# MotherForSmoothie_prefinal.net
KiCad netlist of a schematic drawn in EAGLE
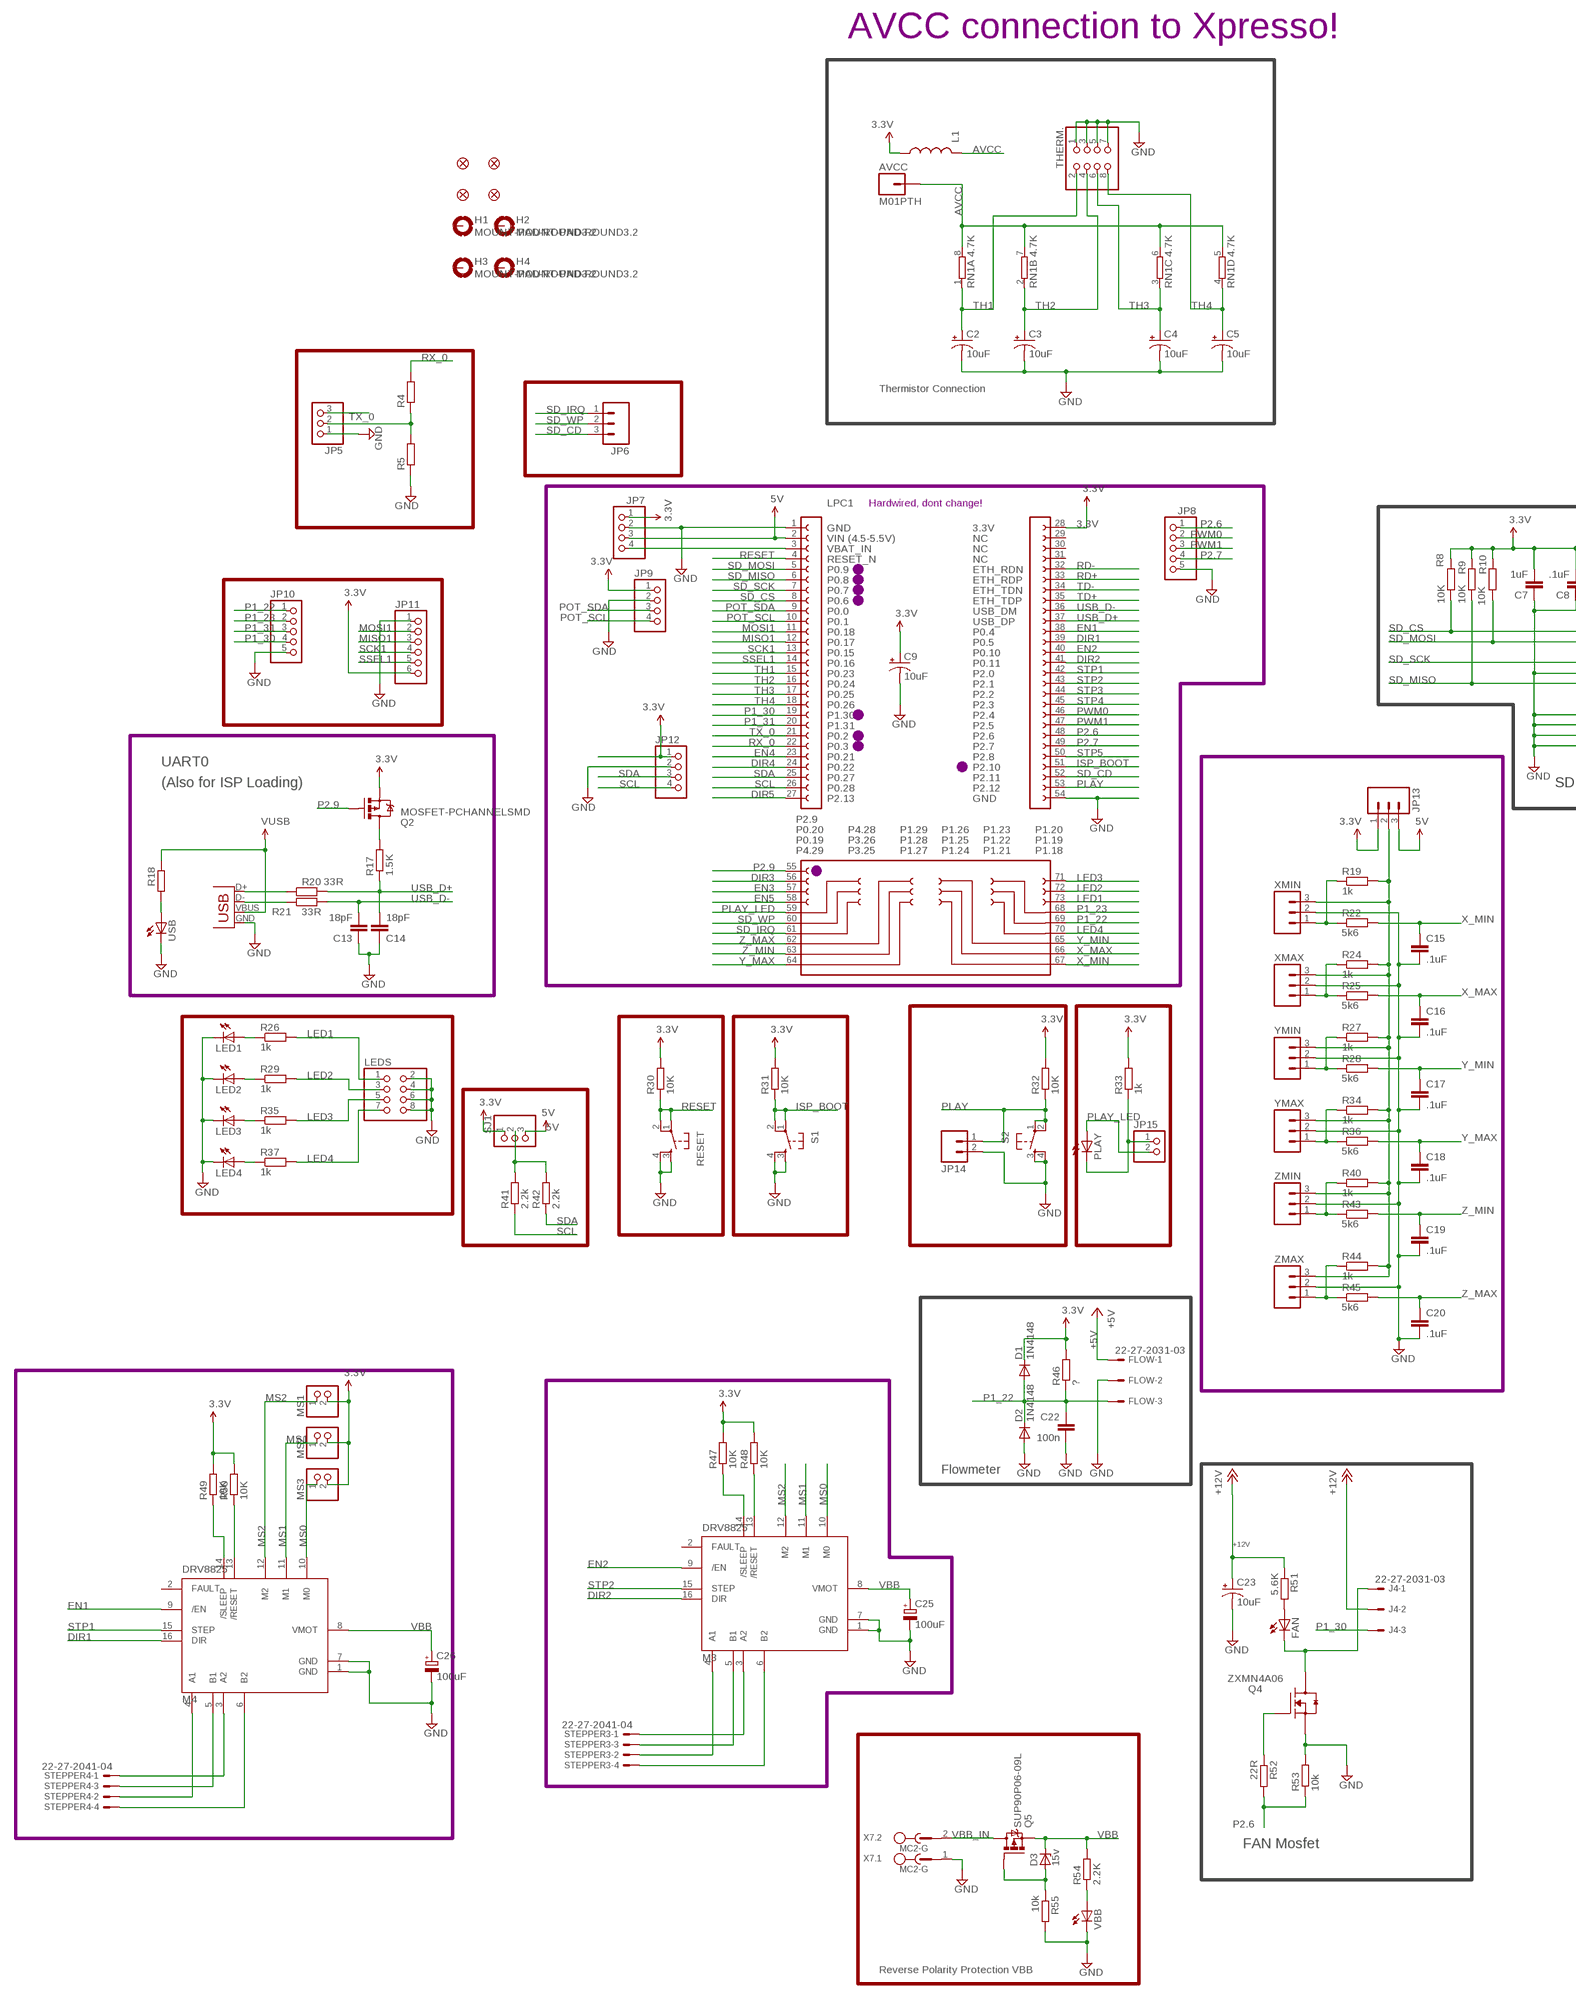
[diagram p0: schematic, sheet 1, part 1 of 2]
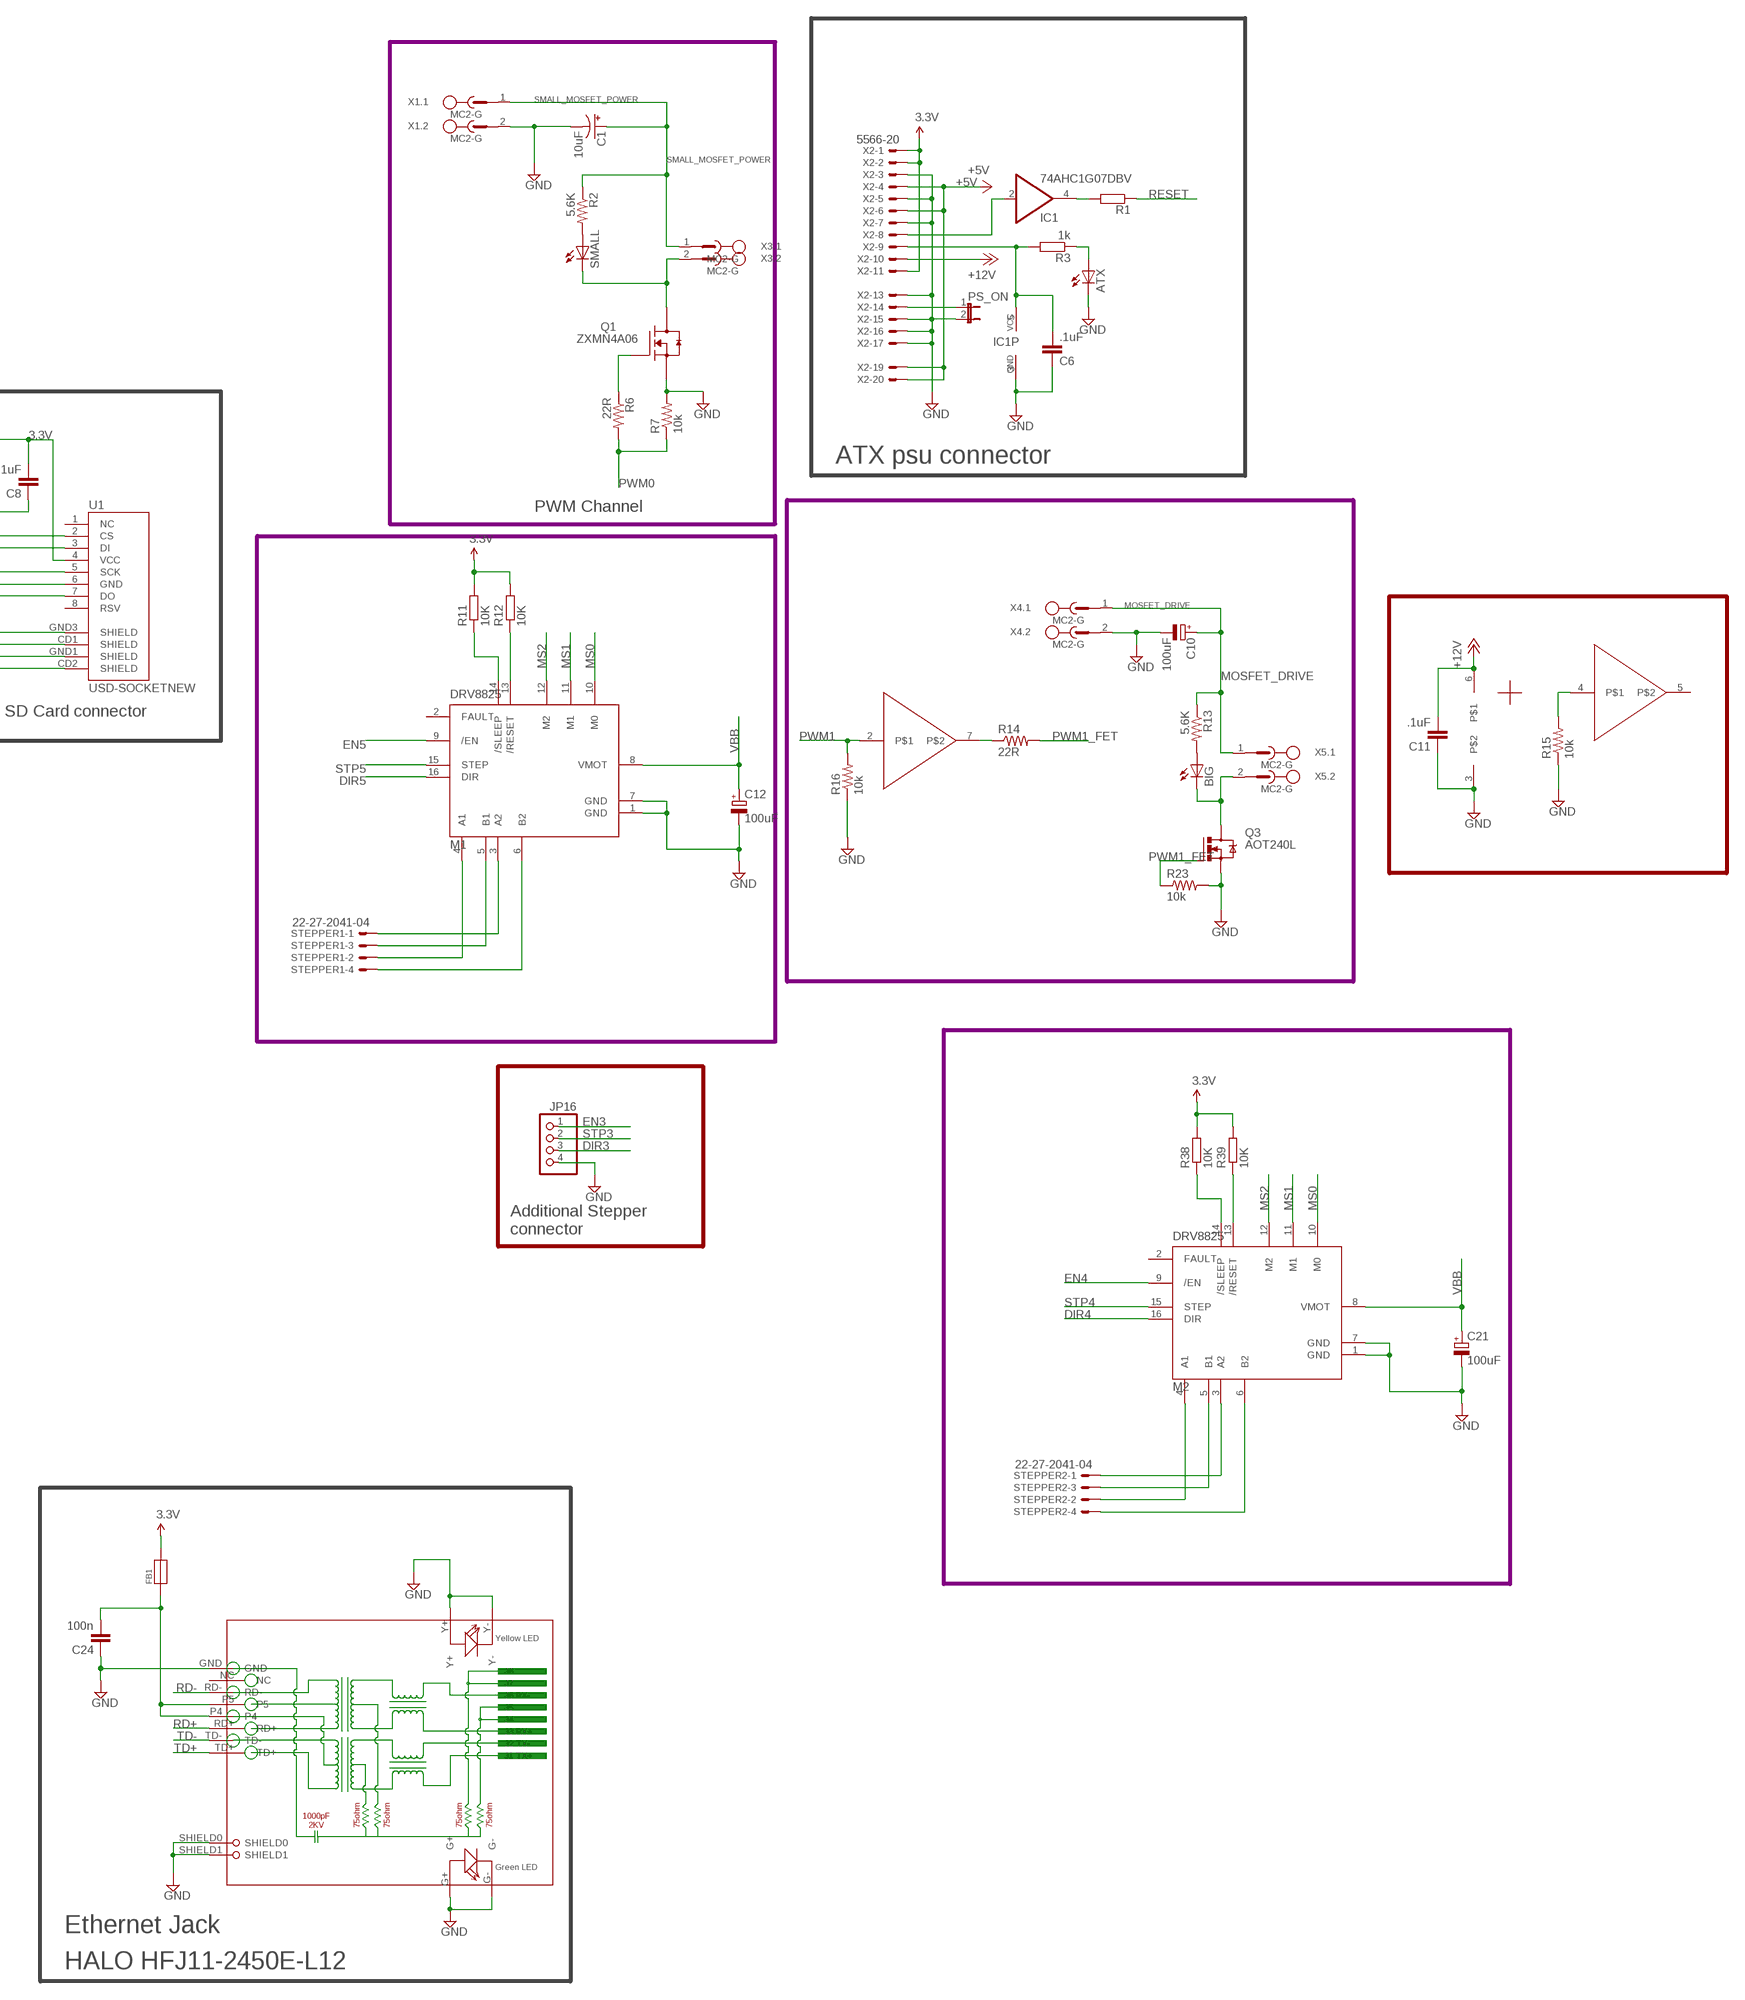
[diagram p1: schematic, sheet 1, part 2 of 2]

(export (version "E")
  (design (tool "Eeschema 10.0.6"))
  (components
    (comp (ref "ATX")
      (value "LEDCHIPLED_0805")
      (footprint "eagle-import:CHIPLED_0805")
      (libsource (lib "eagle-import") (part "LEDCHIPLED_0805"))
    )
    (comp (ref "AVCC")
      (value "M01PTH")
      (footprint "eagle-import:1X01")
      (libsource (lib "eagle-import") (part "M01PTH"))
    )
    (comp (ref "BIG")
      (value "LEDCHIP-LED0805")
      (footprint "eagle-import:CHIP-LED0805")
      (libsource (lib "eagle-import") (part "LEDCHIP-LED0805"))
    )
    (comp (ref "C1")
      (value "10uF")
      (footprint "eagle-import:EIA3216")
      (libsource (lib "eagle-import") (part "CAP_POL1206"))
    )
    (comp (ref "C2")
      (value "10uF")
      (footprint "eagle-import:EIA3216")
      (libsource (lib "eagle-import") (part "CAP_POL1206"))
    )
    (comp (ref "C3")
      (value "10uF")
      (footprint "eagle-import:EIA3216")
      (libsource (lib "eagle-import") (part "CAP_POL1206"))
    )
    (comp (ref "C4")
      (value "10uF")
      (footprint "eagle-import:EIA3216")
      (libsource (lib "eagle-import") (part "CAP_POL1206"))
    )
    (comp (ref "C5")
      (value "10uF")
      (footprint "eagle-import:EIA3216")
      (libsource (lib "eagle-import") (part "CAP_POL1206"))
    )
    (comp (ref "C6")
      (value ".1uF")
      (footprint "eagle-import:C0603")
      (libsource (lib "eagle-import") (part "C-EUC0603"))
    )
    (comp (ref "C7")
      (value "1uF")
      (footprint "eagle-import:C0603")
      (libsource (lib "eagle-import") (part "C-EUC0603"))
    )
    (comp (ref "C8")
      (value ".1uF")
      (footprint "eagle-import:C0603")
      (libsource (lib "eagle-import") (part "C-EUC0603"))
    )
    (comp (ref "C9")
      (value "10uF")
      (footprint "eagle-import:EIA3216")
      (libsource (lib "eagle-import") (part "CAP_POL1206"))
    )
    (comp (ref "C10")
      (value "100uF")
      (footprint "eagle-import:E5-8,5")
      (libsource (lib "eagle-import") (part "CPOL-EUE5-8.5"))
    )
    (comp (ref "C11")
      (value ".1uF")
      (footprint "eagle-import:C0603")
      (libsource (lib "eagle-import") (part "C-EUC0603"))
    )
    (comp (ref "C12")
      (value "100uF")
      (footprint "eagle-import:E5-8,5")
      (libsource (lib "eagle-import") (part "CPOL-EUE5-8.5"))
    )
    (comp (ref "C13")
      (value "18pF")
      (footprint "eagle-import:C0603")
      (libsource (lib "eagle-import") (part "C-EUC0603"))
    )
    (comp (ref "C14")
      (value "18pF")
      (footprint "eagle-import:C0603")
      (libsource (lib "eagle-import") (part "C-EUC0603"))
    )
    (comp (ref "C15")
      (value ".1uF")
      (footprint "eagle-import:C0603")
      (libsource (lib "eagle-import") (part "C-EUC0603"))
    )
    (comp (ref "C16")
      (value ".1uF")
      (footprint "eagle-import:C0603")
      (libsource (lib "eagle-import") (part "C-EUC0603"))
    )
    (comp (ref "C17")
      (value ".1uF")
      (footprint "eagle-import:C0603")
      (libsource (lib "eagle-import") (part "C-EUC0603"))
    )
    (comp (ref "C18")
      (value ".1uF")
      (footprint "eagle-import:C0603")
      (libsource (lib "eagle-import") (part "C-EUC0603"))
    )
    (comp (ref "C19")
      (value ".1uF")
      (footprint "eagle-import:C0603")
      (libsource (lib "eagle-import") (part "C-EUC0603"))
    )
    (comp (ref "C20")
      (value ".1uF")
      (footprint "eagle-import:C0603")
      (libsource (lib "eagle-import") (part "C-EUC0603"))
    )
    (comp (ref "C21")
      (value "100uF")
      (footprint "eagle-import:E5-8,5")
      (libsource (lib "eagle-import") (part "CPOL-EUE5-8.5"))
    )
    (comp (ref "C22")
      (value "100n")
      (footprint "eagle-import:C0603")
      (libsource (lib "eagle-import") (part "C-EUC0603"))
    )
    (comp (ref "C23")
      (value "10uF")
      (footprint "eagle-import:EIA3216")
      (libsource (lib "eagle-import") (part "CAP_POL1206"))
    )
    (comp (ref "C24")
      (value "100n")
      (footprint "eagle-import:C0603")
      (libsource (lib "eagle-import") (part "C-EUC0603"))
    )
    (comp (ref "C25")
      (value "100uF")
      (footprint "eagle-import:E5-8,5")
      (libsource (lib "eagle-import") (part "CPOL-EUE5-8.5"))
    )
    (comp (ref "C26")
      (value "100uF")
      (footprint "eagle-import:E5-8,5")
      (libsource (lib "eagle-import") (part "CPOL-EUE5-8.5"))
    )
    (comp (ref "D1")
      (value "1N4148")
      (footprint "eagle-import:MINIMELF")
      (libsource (lib "eagle-import") (part "DIODE-MINIMELF"))
    )
    (comp (ref "D2")
      (value "1N4148")
      (footprint "eagle-import:MINIMELF")
      (libsource (lib "eagle-import") (part "DIODE-MINIMELF"))
    )
    (comp (ref "D3")
      (value "15v")
      (footprint "eagle-import:SMB")
      (libsource (lib "eagle-import") (part "ZENER-DIODESMB"))
    )
    (comp (ref "FAN")
      (value "LEDCHIPLED_0805")
      (footprint "eagle-import:CHIPLED_0805")
      (libsource (lib "eagle-import") (part "LEDCHIPLED_0805"))
    )
    (comp (ref "FB1")
      (value "FERRITE")
      (footprint "eagle-import:0603")
      (libsource (lib "eagle-import") (part "FERRITE"))
    )
    (comp (ref "FLOW")
      (value "22-27-2031-03")
      (footprint "eagle-import:6410-03")
      (libsource (lib "eagle-import") (part "22-?-0327-2031"))
    )
    (comp (ref "H1")
      (value "MOUNT-PAD-ROUND3.2")
      (footprint "eagle-import:3,2-PAD")
      (libsource (lib "eagle-import") (part "MOUNT-PAD-ROUND3.2"))
    )
    (comp (ref "H2")
      (value "MOUNT-PAD-ROUND3.2")
      (footprint "eagle-import:3,2-PAD")
      (libsource (lib "eagle-import") (part "MOUNT-PAD-ROUND3.2"))
    )
    (comp (ref "H3")
      (value "MOUNT-PAD-ROUND3.2")
      (footprint "eagle-import:3,2-PAD")
      (libsource (lib "eagle-import") (part "MOUNT-PAD-ROUND3.2"))
    )
    (comp (ref "H4")
      (value "MOUNT-PAD-ROUND3.2")
      (footprint "eagle-import:3,2-PAD")
      (libsource (lib "eagle-import") (part "MOUNT-PAD-ROUND3.2"))
    )
    (comp (ref "IC1")
      (value "74AHC1G07DBV")
      (footprint "eagle-import:SOT23-5")
      (libsource (lib "eagle-import") (part "741G07DBVAHC"))
    )
    (comp (ref "IC2")
      (value "TC4427")
      (footprint "eagle-import:SOIC8")
      (libsource (lib "eagle-import") (part "TC4427"))
    )
    (comp (ref "J4")
      (value "22-27-2031-03")
      (footprint "eagle-import:6410-03")
      (libsource (lib "eagle-import") (part "22-?-0327-2031"))
    )
    (comp (ref "JP1")
      (value "FIDUCIAL1X2")
      (footprint "eagle-import:FIDUCIAL-1X2")
      (libsource (lib "eagle-import") (part "FIDUCIAL1X2"))
    )
    (comp (ref "JP2")
      (value "FIDUCIAL1X2")
      (footprint "eagle-import:FIDUCIAL-1X2")
      (libsource (lib "eagle-import") (part "FIDUCIAL1X2"))
    )
    (comp (ref "JP3")
      (value "FIDUCIAL1X2")
      (footprint "eagle-import:FIDUCIAL-1X2")
      (libsource (lib "eagle-import") (part "FIDUCIAL1X2"))
    )
    (comp (ref "JP4")
      (value "FIDUCIAL1X2")
      (footprint "eagle-import:FIDUCIAL-1X2")
      (libsource (lib "eagle-import") (part "FIDUCIAL1X2"))
    )
    (comp (ref "JP5")
      (value "PINHD-1X3_2.54-SMD")
      (footprint "eagle-import:1X03SMD")
      (libsource (lib "eagle-import") (part "PINHD-1X3_2.54-SMD"))
    )
    (comp (ref "JP6")
      (value "M031X03_NO_SILK")
      (footprint "eagle-import:1X03_NO_SILK")
      (libsource (lib "eagle-import") (part "M031X03_NO_SILK"))
    )
    (comp (ref "JP7")
      (value "PINHD-1X4_2.54-SMD")
      (footprint "eagle-import:1X04SMD")
      (libsource (lib "eagle-import") (part "PINHD-1X4_2.54-SMD"))
    )
    (comp (ref "JP8")
      (value "PINHD-1X5_2.54-SMD")
      (footprint "eagle-import:1X05SMD")
      (libsource (lib "eagle-import") (part "PINHD-1X5_2.54-SMD"))
    )
    (comp (ref "JP9")
      (value "PINHD-1X4_2.54-SMD")
      (footprint "eagle-import:1X04SMD")
      (libsource (lib "eagle-import") (part "PINHD-1X4_2.54-SMD"))
    )
    (comp (ref "JP10")
      (value "PINHD-1X5_2.54-SMD")
      (footprint "eagle-import:1X05SMD")
      (libsource (lib "eagle-import") (part "PINHD-1X5_2.54-SMD"))
    )
    (comp (ref "JP11")
      (value "PINHD-1X6_2.54-SMD")
      (footprint "eagle-import:1X06SMD")
      (libsource (lib "eagle-import") (part "PINHD-1X6_2.54-SMD"))
    )
    (comp (ref "JP12")
      (value "PINHD-1X4_2.54-SMD")
      (footprint "eagle-import:1X04SMD")
      (libsource (lib "eagle-import") (part "PINHD-1X4_2.54-SMD"))
    )
    (comp (ref "JP13")
      (value "M031X03_NO_SILK")
      (footprint "eagle-import:1X03_NO_SILK")
      (libsource (lib "eagle-import") (part "M031X03_NO_SILK"))
    )
    (comp (ref "JP14")
      (value "M02PTH")
      (footprint "eagle-import:1X02")
      (libsource (lib "eagle-import") (part "M02PTH"))
    )
    (comp (ref "JP15")
      (value "PINHD-1X2_2.54-SMD")
      (footprint "eagle-import:1X02SMD")
      (libsource (lib "eagle-import") (part "PINHD-1X2_2.54-SMD"))
    )
    (comp (ref "JP16")
      (value "PINHD-1X4_2.54-SMD")
      (footprint "eagle-import:1X04SMD")
      (libsource (lib "eagle-import") (part "PINHD-1X4_2.54-SMD"))
    )
    (comp (ref "L1")
      (value "INDUCTOR0603")
      (footprint "eagle-import:0603")
      (libsource (lib "eagle-import") (part "INDUCTOR0603"))
    )
    (comp (ref "LED1")
      (value "LEDCHIP-LED0805")
      (footprint "eagle-import:CHIP-LED0805")
      (libsource (lib "eagle-import") (part "LEDCHIP-LED0805"))
    )
    (comp (ref "LED2")
      (value "LEDCHIP-LED0805")
      (footprint "eagle-import:CHIP-LED0805")
      (libsource (lib "eagle-import") (part "LEDCHIP-LED0805"))
    )
    (comp (ref "LED3")
      (value "LEDCHIP-LED0805")
      (footprint "eagle-import:CHIP-LED0805")
      (libsource (lib "eagle-import") (part "LEDCHIP-LED0805"))
    )
    (comp (ref "LED4")
      (value "LEDCHIP-LED0805")
      (footprint "eagle-import:CHIP-LED0805")
      (libsource (lib "eagle-import") (part "LEDCHIP-LED0805"))
    )
    (comp (ref "LEDS")
      (value "PINHD-2X4_2.54-SMD")
      (footprint "eagle-import:2X04SMD")
      (libsource (lib "eagle-import") (part "PINHD-2X4_2.54-SMD"))
    )
    (comp (ref "LPC1")
      (value "LPCXPRESSO_LPC1769SMD_PART")
      (footprint "eagle-import:LPCXPRESSO_LPC1769_SMD")
      (libsource (lib "eagle-import") (part "LPCXPRESSO_LPC1769SMD_PART"))
    )
    (comp (ref "M1")
      (value "DRV8825")
      (footprint "eagle-import:DRV8825")
      (libsource (lib "eagle-import") (part "DRV8825"))
    )
    (comp (ref "M2")
      (value "DRV8825")
      (footprint "eagle-import:DRV8825")
      (libsource (lib "eagle-import") (part "DRV8825"))
    )
    (comp (ref "M3")
      (value "DRV8825")
      (footprint "eagle-import:DRV8825")
      (libsource (lib "eagle-import") (part "DRV8825"))
    )
    (comp (ref "M4")
      (value "DRV8825")
      (footprint "eagle-import:DRV8825")
      (libsource (lib "eagle-import") (part "DRV8825"))
    )
    (comp (ref "MS1")
      (value "PINHD-1X2_2.54-SMD")
      (footprint "eagle-import:1X02SMD")
      (libsource (lib "eagle-import") (part "PINHD-1X2_2.54-SMD"))
    )
    (comp (ref "MS2")
      (value "PINHD-1X2_2.54-SMD")
      (footprint "eagle-import:1X02SMD")
      (libsource (lib "eagle-import") (part "PINHD-1X2_2.54-SMD"))
    )
    (comp (ref "MS3")
      (value "PINHD-1X2_2.54-SMD")
      (footprint "eagle-import:1X02SMD")
      (libsource (lib "eagle-import") (part "PINHD-1X2_2.54-SMD"))
    )
    (comp (ref "PLAY")
      (value "LEDCHIPLED_0805")
      (footprint "eagle-import:CHIPLED_0805")
      (libsource (lib "eagle-import") (part "LEDCHIPLED_0805"))
    )
    (comp (ref "PS_ON")
      (value "JP1E")
      (footprint "eagle-import:JP1")
      (libsource (lib "eagle-import") (part "JP1E"))
    )
    (comp (ref "Q1")
      (value "ZXMN4A06")
      (footprint "eagle-import:SOT230P700X160-4N")
      (libsource (lib "eagle-import") (part "MOSFET-NCH_SOT-223"))
    )
    (comp (ref "Q2")
      (value "MOSFET-PCHANNELSMD")
      (footprint "eagle-import:SOT23-3")
      (libsource (lib "eagle-import") (part "MOSFET-PCHANNELSMD"))
    )
    (comp (ref "Q3")
      (value "AOT240L")
      (footprint "eagle-import:TO220BV")
      (libsource (lib "eagle-import") (part "IRF540"))
    )
    (comp (ref "Q4")
      (value "ZXMN4A06")
      (footprint "eagle-import:SOT230P700X160-4N")
      (libsource (lib "eagle-import") (part "MOSFET-NCH_SOT-223"))
    )
    (comp (ref "Q5")
      (value "SUP90P06-09L")
      (footprint "eagle-import:TO220BV")
      (libsource (lib "eagle-import") (part "IRF9530"))
    )
    (comp (ref "R1")
      (value "R-EU_R0603")
      (footprint "eagle-import:R0603")
      (libsource (lib "eagle-import") (part "R-EU_R0603"))
    )
    (comp (ref "R2")
      (value "5.6K")
      (footprint "eagle-import:R0603")
      (libsource (lib "eagle-import") (part "R-US_R0603"))
    )
    (comp (ref "R3")
      (value "1k")
      (footprint "eagle-import:R0603")
      (libsource (lib "eagle-import") (part "R-EU_R0603"))
    )
    (comp (ref "R4")
      (value "R-EU_R0603")
      (footprint "eagle-import:R0603")
      (libsource (lib "eagle-import") (part "R-EU_R0603"))
    )
    (comp (ref "R5")
      (value "R-EU_R0603")
      (footprint "eagle-import:R0603")
      (libsource (lib "eagle-import") (part "R-EU_R0603"))
    )
    (comp (ref "R6")
      (value "22R")
      (footprint "eagle-import:R0603")
      (libsource (lib "eagle-import") (part "R-US_R0603"))
    )
    (comp (ref "R7")
      (value "10k")
      (footprint "eagle-import:R0603")
      (libsource (lib "eagle-import") (part "R-US_R0603"))
    )
    (comp (ref "R8")
      (value "10K")
      (footprint "eagle-import:R0603")
      (libsource (lib "eagle-import") (part "R-EU_R0603"))
    )
    (comp (ref "R9")
      (value "10K")
      (footprint "eagle-import:R0603")
      (libsource (lib "eagle-import") (part "R-EU_R0603"))
    )
    (comp (ref "R10")
      (value "10K")
      (footprint "eagle-import:R0603")
      (libsource (lib "eagle-import") (part "R-EU_R0603"))
    )
    (comp (ref "R11")
      (value "10K")
      (footprint "eagle-import:R0603")
      (libsource (lib "eagle-import") (part "R-EU_R0603"))
    )
    (comp (ref "R12")
      (value "10K")
      (footprint "eagle-import:R0603")
      (libsource (lib "eagle-import") (part "R-EU_R0603"))
    )
    (comp (ref "R13")
      (value "5.6K")
      (footprint "eagle-import:R0603")
      (libsource (lib "eagle-import") (part "R-US_R0603"))
    )
    (comp (ref "R14")
      (value "22R")
      (footprint "eagle-import:R0603")
      (libsource (lib "eagle-import") (part "R-US_R0603"))
    )
    (comp (ref "R15")
      (value "10k")
      (footprint "eagle-import:R0603")
      (libsource (lib "eagle-import") (part "R-US_R0603"))
    )
    (comp (ref "R16")
      (value "10k")
      (footprint "eagle-import:R0603")
      (libsource (lib "eagle-import") (part "R-US_R0603"))
    )
    (comp (ref "R17")
      (value "1.5K")
      (footprint "eagle-import:R0603")
      (libsource (lib "eagle-import") (part "R-EU_R0603"))
    )
    (comp (ref "R18")
      (value "R-EU_R0603")
      (footprint "eagle-import:R0603")
      (libsource (lib "eagle-import") (part "R-EU_R0603"))
    )
    (comp (ref "R19")
      (value "1k")
      (footprint "eagle-import:R0603")
      (libsource (lib "eagle-import") (part "R-EU_R0603"))
    )
    (comp (ref "R20")
      (value "33R")
      (footprint "eagle-import:R0603")
      (libsource (lib "eagle-import") (part "R-EU_R0603"))
    )
    (comp (ref "R21")
      (value "33R")
      (footprint "eagle-import:R0603")
      (libsource (lib "eagle-import") (part "R-EU_R0603"))
    )
    (comp (ref "R22")
      (value "5k6")
      (footprint "eagle-import:R0603")
      (libsource (lib "eagle-import") (part "R-EU_R0603"))
    )
    (comp (ref "R23")
      (value "10k")
      (footprint "eagle-import:R0603")
      (libsource (lib "eagle-import") (part "R-US_R0603"))
    )
    (comp (ref "R24")
      (value "1k")
      (footprint "eagle-import:R0603")
      (libsource (lib "eagle-import") (part "R-EU_R0603"))
    )
    (comp (ref "R25")
      (value "5k6")
      (footprint "eagle-import:R0603")
      (libsource (lib "eagle-import") (part "R-EU_R0603"))
    )
    (comp (ref "R26")
      (value "1k")
      (footprint "eagle-import:R0603")
      (libsource (lib "eagle-import") (part "R-EU_R0603"))
    )
    (comp (ref "R27")
      (value "1k")
      (footprint "eagle-import:R0603")
      (libsource (lib "eagle-import") (part "R-EU_R0603"))
    )
    (comp (ref "R28")
      (value "5k6")
      (footprint "eagle-import:R0603")
      (libsource (lib "eagle-import") (part "R-EU_R0603"))
    )
    (comp (ref "R29")
      (value "1k")
      (footprint "eagle-import:R0603")
      (libsource (lib "eagle-import") (part "R-EU_R0603"))
    )
    (comp (ref "R30")
      (value "10K")
      (footprint "eagle-import:R0603")
      (libsource (lib "eagle-import") (part "R-EU_R0603"))
    )
    (comp (ref "R31")
      (value "10K")
      (footprint "eagle-import:R0603")
      (libsource (lib "eagle-import") (part "R-EU_R0603"))
    )
    (comp (ref "R32")
      (value "10K")
      (footprint "eagle-import:R0603")
      (libsource (lib "eagle-import") (part "R-EU_R0603"))
    )
    (comp (ref "R33")
      (value "1k")
      (footprint "eagle-import:R0603")
      (libsource (lib "eagle-import") (part "R-EU_R0603"))
    )
    (comp (ref "R34")
      (value "1k")
      (footprint "eagle-import:R0603")
      (libsource (lib "eagle-import") (part "R-EU_R0603"))
    )
    (comp (ref "R35")
      (value "1k")
      (footprint "eagle-import:R0603")
      (libsource (lib "eagle-import") (part "R-EU_R0603"))
    )
    (comp (ref "R36")
      (value "5k6")
      (footprint "eagle-import:R0603")
      (libsource (lib "eagle-import") (part "R-EU_R0603"))
    )
    (comp (ref "R37")
      (value "1k")
      (footprint "eagle-import:R0603")
      (libsource (lib "eagle-import") (part "R-EU_R0603"))
    )
    (comp (ref "R38")
      (value "10K")
      (footprint "eagle-import:R0603")
      (libsource (lib "eagle-import") (part "R-EU_R0603"))
    )
    (comp (ref "R39")
      (value "10K")
      (footprint "eagle-import:R0603")
      (libsource (lib "eagle-import") (part "R-EU_R0603"))
    )
    (comp (ref "R40")
      (value "1k")
      (footprint "eagle-import:R0603")
      (libsource (lib "eagle-import") (part "R-EU_R0603"))
    )
    (comp (ref "R41")
      (value "2.2k")
      (footprint "eagle-import:R0603")
      (libsource (lib "eagle-import") (part "R-EU_R0603"))
    )
    (comp (ref "R42")
      (value "2.2k")
      (footprint "eagle-import:R0603")
      (libsource (lib "eagle-import") (part "R-EU_R0603"))
    )
    (comp (ref "R43")
      (value "5k6")
      (footprint "eagle-import:R0603")
      (libsource (lib "eagle-import") (part "R-EU_R0603"))
    )
    (comp (ref "R44")
      (value "1k")
      (footprint "eagle-import:R0603")
      (libsource (lib "eagle-import") (part "R-EU_R0603"))
    )
    (comp (ref "R45")
      (value "5k6")
      (footprint "eagle-import:R0603")
      (libsource (lib "eagle-import") (part "R-EU_R0603"))
    )
    (comp (ref "R46")
      (value "?")
      (footprint "eagle-import:R0603")
      (libsource (lib "eagle-import") (part "R-EU_R0603"))
    )
    (comp (ref "R47")
      (value "10K")
      (footprint "eagle-import:R0603")
      (libsource (lib "eagle-import") (part "R-EU_R0603"))
    )
    (comp (ref "R48")
      (value "10K")
      (footprint "eagle-import:R0603")
      (libsource (lib "eagle-import") (part "R-EU_R0603"))
    )
    (comp (ref "R49")
      (value "10K")
      (footprint "eagle-import:R0603")
      (libsource (lib "eagle-import") (part "R-EU_R0603"))
    )
    (comp (ref "R50")
      (value "10K")
      (footprint "eagle-import:R0603")
      (libsource (lib "eagle-import") (part "R-EU_R0603"))
    )
    (comp (ref "R51")
      (value "5.6K")
      (footprint "eagle-import:R0603")
      (libsource (lib "eagle-import") (part "R-EU_R0603"))
    )
    (comp (ref "R52")
      (value "22R")
      (footprint "eagle-import:R0603")
      (libsource (lib "eagle-import") (part "R-EU_R0603"))
    )
    (comp (ref "R53")
      (value "10k")
      (footprint "eagle-import:R0603")
      (libsource (lib "eagle-import") (part "R-EU_R0603"))
    )
    (comp (ref "R54")
      (value "2.2K")
      (footprint "eagle-import:R0603")
      (libsource (lib "eagle-import") (part "R-EU_R0603"))
    )
    (comp (ref "R55")
      (value "10k")
      (footprint "eagle-import:R0603")
      (libsource (lib "eagle-import") (part "R-EU_R0603"))
    )
    (comp (ref "RESET")
      (value "TAC_SWITCHSMD")
      (footprint "eagle-import:TACTILE_SWITCH_SMD")
      (libsource (lib "eagle-import") (part "TAC_SWITCHSMD"))
    )
    (comp (ref "RJ1")
      (value "HR911105A")
      (footprint "eagle-import:HR911105A")
      (libsource (lib "eagle-import") (part "HR911105A"))
    )
    (comp (ref "RN1")
      (value "4.7K")
      (footprint "eagle-import:0603-ARV")
      (libsource (lib "eagle-import") (part "4R-N0603-ARV"))
    )
    (comp (ref "S1")
      (value "TAC_SWITCHSMD")
      (footprint "eagle-import:TACTILE_SWITCH_SMD")
      (libsource (lib "eagle-import") (part "TAC_SWITCHSMD"))
    )
    (comp (ref "S2")
      (value "TAC_SWITCHSMD")
      (footprint "eagle-import:TACTILE_SWITCH_SMD")
      (libsource (lib "eagle-import") (part "TAC_SWITCHSMD"))
    )
    (comp (ref "SJ1")
      (value "PINHD-1X3_2.54-SMD")
      (footprint "eagle-import:1X03SMD")
      (libsource (lib "eagle-import") (part "PINHD-1X3_2.54-SMD"))
    )
    (comp (ref "SMALL")
      (value "LEDCHIP-LED0805")
      (footprint "eagle-import:CHIP-LED0805")
      (libsource (lib "eagle-import") (part "LEDCHIP-LED0805"))
    )
    (comp (ref "STEPPER1")
      (value "22-27-2041-04")
      (footprint "eagle-import:6410-04")
      (libsource (lib "eagle-import") (part "22-?-0427-2041"))
    )
    (comp (ref "STEPPER2")
      (value "22-27-2041-04")
      (footprint "eagle-import:6410-04")
      (libsource (lib "eagle-import") (part "22-?-0427-2041"))
    )
    (comp (ref "STEPPER3")
      (value "22-27-2041-04")
      (footprint "eagle-import:6410-04")
      (libsource (lib "eagle-import") (part "22-?-0427-2041"))
    )
    (comp (ref "STEPPER4")
      (value "22-27-2041-04")
      (footprint "eagle-import:6410-04")
      (libsource (lib "eagle-import") (part "22-?-0427-2041"))
    )
    (comp (ref "THERM.")
      (value "PINHD-2X4MICROMATCH-SMD")
      (footprint "eagle-import:SMDTOP8")
      (libsource (lib "eagle-import") (part "PINHD-2X4MICROMATCH-SMD"))
    )
    (comp (ref "U1")
      (value "USD-SOCKETNEW")
      (footprint "eagle-import:MICRO-SD-SOCKET-PP")
      (libsource (lib "eagle-import") (part "USD-SOCKETNEW"))
    )
    (comp (ref "USB")
      (value "LEDCHIPLED_0805")
      (footprint "eagle-import:CHIPLED_0805")
      (libsource (lib "eagle-import") (part "LEDCHIPLED_0805"))
    )
    (comp (ref "VBB")
      (value "LEDCHIPLED_0805")
      (footprint "eagle-import:CHIPLED_0805")
      (libsource (lib "eagle-import") (part "LEDCHIPLED_0805"))
    )
    (comp (ref "X1")
      (value "MC2-G")
      (footprint "eagle-import:MC2-G")
      (libsource (lib "eagle-import") (part "MC2-G"))
    )
    (comp (ref "X2")
      (value "5566-20")
      (footprint "eagle-import:5566-20")
      (libsource (lib "eagle-import") (part "5566-20"))
    )
    (comp (ref "X3")
      (value "MC2-G")
      (footprint "eagle-import:MC2-G")
      (libsource (lib "eagle-import") (part "MC2-G"))
    )
    (comp (ref "X4")
      (value "MC2-G")
      (footprint "eagle-import:MC2-G")
      (libsource (lib "eagle-import") (part "MC2-G"))
    )
    (comp (ref "X5")
      (value "MC2-G")
      (footprint "eagle-import:MC2-G")
      (libsource (lib "eagle-import") (part "MC2-G"))
    )
    (comp (ref "X6")
      (value "USB-MICROB")
      (footprint "eagle-import:USB-MICROB")
      (libsource (lib "eagle-import") (part "USB-MICROB"))
    )
    (comp (ref "X7")
      (value "MC2-G")
      (footprint "eagle-import:MC2-G")
      (libsource (lib "eagle-import") (part "MC2-G"))
    )
    (comp (ref "XMAX")
      (value "M031X03_NO_SILK")
      (footprint "eagle-import:1X03_NO_SILK")
      (libsource (lib "eagle-import") (part "M031X03_NO_SILK"))
    )
    (comp (ref "XMIN")
      (value "M031X03_NO_SILK")
      (footprint "eagle-import:1X03_NO_SILK")
      (libsource (lib "eagle-import") (part "M031X03_NO_SILK"))
    )
    (comp (ref "YMAX")
      (value "M031X03_NO_SILK")
      (footprint "eagle-import:1X03_NO_SILK")
      (libsource (lib "eagle-import") (part "M031X03_NO_SILK"))
    )
    (comp (ref "YMIN")
      (value "M031X03_NO_SILK")
      (footprint "eagle-import:1X03_NO_SILK")
      (libsource (lib "eagle-import") (part "M031X03_NO_SILK"))
    )
    (comp (ref "ZMAX")
      (value "M031X03_NO_SILK")
      (footprint "eagle-import:1X03_NO_SILK")
      (libsource (lib "eagle-import") (part "M031X03_NO_SILK"))
    )
    (comp (ref "ZMIN")
      (value "M031X03_NO_SILK")
      (footprint "eagle-import:1X03_NO_SILK")
      (libsource (lib "eagle-import") (part "M031X03_NO_SILK"))
    )
  )
  (nets
    (net (code "1") (name "+5V") (class "Default")
      (node (ref "FLOW") (pin "1") (pinfunction "S_1") (pintype "passive"))
      (node (ref "X2") (pin "19") (pinfunction "S_19") (pintype "passive"))
      (node (ref "X2") (pin "20") (pinfunction "S_20") (pintype "passive"))
      (node (ref "X2") (pin "4") (pinfunction "S_4") (pintype "passive"))
      (node (ref "X2") (pin "6") (pinfunction "S_6") (pintype "passive"))
    )
    (net (code "2") (name "+12V") (class "Default")
      (node (ref "C11") (pin "2") (pinfunction "2_2") (pintype "passive"))
      (node (ref "C23") (pin "A") (pinfunction "+_A") (pintype "passive"))
      (node (ref "IC2") (pin "6") (pinfunction "P$1_6") (pintype "bidirectional"))
      (node (ref "J4") (pin "2") (pinfunction "S_2") (pintype "passive"))
      (node (ref "R51") (pin "1") (pinfunction "1_1") (pintype "passive"))
      (node (ref "X2") (pin "10") (pinfunction "S_10") (pintype "passive"))
    )
    (net (code "3") (name "/AVCC") (class "Default")
      (node (ref "AVCC") (pin "1") (pinfunction "1_1") (pintype "passive"))
      (node (ref "L1") (pin "1") (pinfunction "1_1") (pintype "passive"))
      (node (ref "RN1") (pin "5") (pinfunction "2_5") (pintype "passive"))
      (node (ref "RN1") (pin "6") (pinfunction "2_6") (pintype "passive"))
      (node (ref "RN1") (pin "7") (pinfunction "2_7") (pintype "passive"))
      (node (ref "RN1") (pin "8") (pinfunction "2_8") (pintype "passive"))
    )
    (net (code "4") (name "/DIR1") (class "Default")
      (node (ref "LPC1") (pin "39") (pinfunction "39_39") (pintype "passive"))
      (node (ref "M4") (pin "16") (pinfunction "DIR_16") (pintype "input"))
    )
    (net (code "5") (name "/DIR2") (class "Default")
      (node (ref "LPC1") (pin "41") (pinfunction "41_41") (pintype "passive"))
      (node (ref "M3") (pin "16") (pinfunction "DIR_16") (pintype "input"))
    )
    (net (code "6") (name "/DIR3") (class "Default")
      (node (ref "JP16") (pin "3") (pinfunction "3_3") (pintype "passive"))
      (node (ref "LPC1") (pin "56") (pinfunction "56_56") (pintype "passive"))
    )
    (net (code "7") (name "/DIR4") (class "Default")
      (node (ref "LPC1") (pin "24") (pinfunction "24_24") (pintype "passive"))
      (node (ref "M2") (pin "16") (pinfunction "DIR_16") (pintype "input"))
    )
    (net (code "8") (name "/DIR5") (class "Default")
      (node (ref "LPC1") (pin "27") (pinfunction "27_27") (pintype "passive"))
      (node (ref "M1") (pin "16") (pinfunction "DIR_16") (pintype "input"))
    )
    (net (code "9") (name "/EN1") (class "Default")
      (node (ref "LPC1") (pin "38") (pinfunction "38_38") (pintype "passive"))
      (node (ref "M4") (pin "9") (pinfunction "/EN_9") (pintype "input"))
    )
    (net (code "10") (name "/EN2") (class "Default")
      (node (ref "LPC1") (pin "40") (pinfunction "40_40") (pintype "passive"))
      (node (ref "M3") (pin "9") (pinfunction "/EN_9") (pintype "input"))
    )
    (net (code "11") (name "/EN3") (class "Default")
      (node (ref "JP16") (pin "1") (pinfunction "1_1") (pintype "passive"))
      (node (ref "LPC1") (pin "57") (pinfunction "57_57") (pintype "passive"))
    )
    (net (code "12") (name "/EN4") (class "Default")
      (node (ref "LPC1") (pin "23") (pinfunction "23_23") (pintype "passive"))
      (node (ref "M2") (pin "9") (pinfunction "/EN_9") (pintype "input"))
    )
    (net (code "13") (name "/EN5") (class "Default")
      (node (ref "LPC1") (pin "58") (pinfunction "58_58") (pintype "passive"))
      (node (ref "M1") (pin "9") (pinfunction "/EN_9") (pintype "input"))
    )
    (net (code "14") (name "/ISP_BOOT") (class "Default")
      (node (ref "LPC1") (pin "51") (pinfunction "51_51") (pintype "passive"))
      (node (ref "R31") (pin "1") (pinfunction "1_1") (pintype "passive"))
      (node (ref "S1") (pin "1") (pinfunction "1_1") (pintype "passive"))
      (node (ref "S1") (pin "2") (pinfunction "2_2") (pintype "passive"))
    )
    (net (code "15") (name "/LED1") (class "Default")
      (node (ref "LEDS") (pin "1") (pinfunction "1_1") (pintype "passive"))
      (node (ref "LPC1") (pin "73") (pinfunction "73_73") (pintype "passive"))
      (node (ref "R26") (pin "2") (pinfunction "2_2") (pintype "passive"))
    )
    (net (code "16") (name "/LED2") (class "Default")
      (node (ref "LEDS") (pin "3") (pinfunction "3_3") (pintype "passive"))
      (node (ref "LPC1") (pin "72") (pinfunction "72_72") (pintype "passive"))
      (node (ref "R29") (pin "2") (pinfunction "2_2") (pintype "passive"))
    )
    (net (code "17") (name "/LED3") (class "Default")
      (node (ref "LEDS") (pin "5") (pinfunction "5_5") (pintype "passive"))
      (node (ref "LPC1") (pin "71") (pinfunction "71_71") (pintype "passive"))
      (node (ref "R35") (pin "2") (pinfunction "2_2") (pintype "passive"))
    )
    (net (code "18") (name "/LED4") (class "Default")
      (node (ref "LEDS") (pin "7") (pinfunction "7_7") (pintype "passive"))
      (node (ref "LPC1") (pin "70") (pinfunction "70_70") (pintype "passive"))
      (node (ref "R37") (pin "2") (pinfunction "2_2") (pintype "passive"))
    )
    (net (code "19") (name "/MISO1") (class "Default")
      (node (ref "JP11") (pin "3") (pinfunction "3_3") (pintype "passive"))
      (node (ref "LPC1") (pin "12") (pinfunction "12_12") (pintype "passive"))
    )
    (net (code "20") (name "/MOSFET_DRIVE") (class "Default")
      (node (ref "C10") (pin "+") (pinfunction "+_+") (pintype "passive"))
      (node (ref "R13") (pin "1") (pinfunction "1_1") (pintype "passive"))
      (node (ref "X4") (pin "1") (pinfunction "SK_1") (pintype "passive"))
      (node (ref "X5") (pin "1") (pinfunction "SK_1") (pintype "passive"))
    )
    (net (code "21") (name "/MOSI1") (class "Default")
      (node (ref "JP11") (pin "2") (pinfunction "2_2") (pintype "passive"))
      (node (ref "LPC1") (pin "11") (pinfunction "11_11") (pintype "passive"))
    )
    (net (code "22") (name "/MS0") (class "Default")
      (node (ref "M1") (pin "10") (pinfunction "M0_10") (pintype "input"))
      (node (ref "M2") (pin "10") (pinfunction "M0_10") (pintype "input"))
      (node (ref "M3") (pin "10") (pinfunction "M0_10") (pintype "input"))
      (node (ref "M4") (pin "10") (pinfunction "M0_10") (pintype "input"))
      (node (ref "MS3") (pin "1") (pinfunction "1_1") (pintype "passive"))
    )
    (net (code "23") (name "/MS1") (class "Default")
      (node (ref "M1") (pin "11") (pinfunction "M1_11") (pintype "input"))
      (node (ref "M2") (pin "11") (pinfunction "M1_11") (pintype "input"))
      (node (ref "M3") (pin "11") (pinfunction "M1_11") (pintype "input"))
      (node (ref "M4") (pin "11") (pinfunction "M1_11") (pintype "input"))
      (node (ref "MS2") (pin "1") (pinfunction "1_1") (pintype "passive"))
    )
    (net (code "24") (name "/MS2") (class "Default")
      (node (ref "M1") (pin "12") (pinfunction "M2_12") (pintype "input"))
      (node (ref "M2") (pin "12") (pinfunction "M2_12") (pintype "input"))
      (node (ref "M3") (pin "12") (pinfunction "M2_12") (pintype "input"))
      (node (ref "M4") (pin "12") (pinfunction "M2_12") (pintype "input"))
      (node (ref "MS1") (pin "1") (pinfunction "1_1") (pintype "passive"))
    )
    (net (code "25") (name "/P1_22") (class "Default")
      (node (ref "C22") (pin "1") (pinfunction "1_1") (pintype "passive"))
      (node (ref "D1") (pin "A") (pinfunction "A_A") (pintype "passive"))
      (node (ref "D2") (pin "C") (pinfunction "C_C") (pintype "passive"))
      (node (ref "FLOW") (pin "3") (pinfunction "S_3") (pintype "passive"))
      (node (ref "JP10") (pin "1") (pinfunction "1_1") (pintype "passive"))
      (node (ref "LPC1") (pin "69") (pinfunction "69_69") (pintype "passive"))
      (node (ref "R46") (pin "1") (pinfunction "1_1") (pintype "passive"))
    )
    (net (code "26") (name "/P1_23") (class "Default")
      (node (ref "JP10") (pin "2") (pinfunction "2_2") (pintype "passive"))
      (node (ref "LPC1") (pin "68") (pinfunction "68_68") (pintype "passive"))
    )
    (net (code "27") (name "/P1_30") (class "Default")
      (node (ref "J4") (pin "3") (pinfunction "S_3") (pintype "passive"))
      (node (ref "JP10") (pin "4") (pinfunction "4_4") (pintype "passive"))
      (node (ref "LPC1") (pin "19") (pinfunction "19_19") (pintype "passive"))
    )
    (net (code "28") (name "/P1_31") (class "Default")
      (node (ref "JP10") (pin "3") (pinfunction "3_3") (pintype "passive"))
      (node (ref "LPC1") (pin "20") (pinfunction "20_20") (pintype "passive"))
    )
    (net (code "29") (name "/P2.6") (class "Default")
      (node (ref "JP8") (pin "1") (pinfunction "1_1") (pintype "passive"))
      (node (ref "LPC1") (pin "48") (pinfunction "48_48") (pintype "passive"))
      (node (ref "R52") (pin "2") (pinfunction "2_2") (pintype "passive"))
      (node (ref "R53") (pin "1") (pinfunction "1_1") (pintype "passive"))
    )
    (net (code "30") (name "/P2.7") (class "Default")
      (node (ref "JP8") (pin "4") (pinfunction "4_4") (pintype "passive"))
      (node (ref "LPC1") (pin "49") (pinfunction "49_49") (pintype "passive"))
    )
    (net (code "31") (name "/P2.9") (class "Default")
      (node (ref "LPC1") (pin "55") (pinfunction "55_55") (pintype "passive"))
      (node (ref "Q2") (pin "1") (pinfunction "G_1") (pintype "passive"))
    )
    (net (code "32") (name "/PLAY") (class "Default")
      (node (ref "JP14") (pin "1") (pinfunction "1_1") (pintype "passive"))
      (node (ref "LPC1") (pin "53") (pinfunction "53_53") (pintype "passive"))
      (node (ref "R32") (pin "1") (pinfunction "1_1") (pintype "passive"))
      (node (ref "S2") (pin "1") (pinfunction "1_1") (pintype "passive"))
      (node (ref "S2") (pin "2") (pinfunction "2_2") (pintype "passive"))
    )
    (net (code "33") (name "/PLAY_LED") (class "Default")
      (node (ref "JP15") (pin "2") (pinfunction "2_2") (pintype "passive"))
      (node (ref "LPC1") (pin "59") (pinfunction "59_59") (pintype "passive"))
      (node (ref "PLAY") (pin "A") (pinfunction "A_A") (pintype "passive"))
    )
    (net (code "34") (name "/POT_SCL") (class "Default")
      (node (ref "JP9") (pin "4") (pinfunction "4_4") (pintype "passive"))
      (node (ref "LPC1") (pin "10") (pinfunction "10_10") (pintype "passive"))
    )
    (net (code "35") (name "/POT_SDA") (class "Default")
      (node (ref "JP9") (pin "3") (pinfunction "3_3") (pintype "passive"))
      (node (ref "LPC1") (pin "9") (pinfunction "9_9") (pintype "passive"))
    )
    (net (code "36") (name "/PWM0") (class "Default")
      (node (ref "JP8") (pin "2") (pinfunction "2_2") (pintype "passive"))
      (node (ref "LPC1") (pin "46") (pinfunction "46_46") (pintype "passive"))
      (node (ref "R6") (pin "2") (pinfunction "2_2") (pintype "passive"))
      (node (ref "R7") (pin "1") (pinfunction "1_1") (pintype "passive"))
    )
    (net (code "37") (name "/PWM1") (class "Default")
      (node (ref "IC2") (pin "2") (pinfunction "P$1_2") (pintype "bidirectional"))
      (node (ref "JP8") (pin "3") (pinfunction "3_3") (pintype "passive"))
      (node (ref "LPC1") (pin "47") (pinfunction "47_47") (pintype "passive"))
      (node (ref "R16") (pin "2") (pinfunction "2_2") (pintype "passive"))
    )
    (net (code "38") (name "/PWM1_FET") (class "Default")
      (node (ref "Q3") (pin "G") (pinfunction "G_G") (pintype "passive"))
      (node (ref "R14") (pin "2") (pinfunction "2_2") (pintype "passive"))
      (node (ref "R23") (pin "1") (pinfunction "1_1") (pintype "passive"))
    )
    (net (code "39") (name "/RD+") (class "Default")
      (node (ref "LPC1") (pin "33") (pinfunction "33_33") (pintype "passive"))
      (node (ref "RJ1") (pin "RD+") (pinfunction "RD+_RD+") (pintype "bidirectional"))
    )
    (net (code "40") (name "/RD-") (class "Default")
      (node (ref "LPC1") (pin "32") (pinfunction "32_32") (pintype "passive"))
      (node (ref "RJ1") (pin "RD-") (pinfunction "RD-_RD-") (pintype "bidirectional"))
    )
    (net (code "41") (name "/RESET") (class "Default")
      (node (ref "LPC1") (pin "4") (pinfunction "4_4") (pintype "passive"))
      (node (ref "R1") (pin "1") (pinfunction "1_1") (pintype "passive"))
      (node (ref "R30") (pin "1") (pinfunction "1_1") (pintype "passive"))
      (node (ref "RESET") (pin "1") (pinfunction "1_1") (pintype "passive"))
      (node (ref "RESET") (pin "2") (pinfunction "2_2") (pintype "passive"))
    )
    (net (code "42") (name "/RX_0") (class "Default")
      (node (ref "LPC1") (pin "22") (pinfunction "22_22") (pintype "passive"))
      (node (ref "R4") (pin "2") (pinfunction "2_2") (pintype "passive"))
    )
    (net (code "43") (name "/SCK1") (class "Default")
      (node (ref "JP11") (pin "4") (pinfunction "4_4") (pintype "passive"))
      (node (ref "LPC1") (pin "13") (pinfunction "13_13") (pintype "passive"))
    )
    (net (code "44") (name "/SCL") (class "Default")
      (node (ref "JP12") (pin "4") (pinfunction "4_4") (pintype "passive"))
      (node (ref "LPC1") (pin "26") (pinfunction "26_26") (pintype "passive"))
      (node (ref "R41") (pin "1") (pinfunction "1_1") (pintype "passive"))
    )
    (net (code "45") (name "/SDA") (class "Default")
      (node (ref "JP12") (pin "3") (pinfunction "3_3") (pintype "passive"))
      (node (ref "LPC1") (pin "25") (pinfunction "25_25") (pintype "passive"))
      (node (ref "R42") (pin "1") (pinfunction "1_1") (pintype "passive"))
    )
    (net (code "46") (name "/SD_CD") (class "Default")
      (node (ref "JP6") (pin "3") (pinfunction "3_3") (pintype "passive"))
      (node (ref "LPC1") (pin "52") (pinfunction "52_52") (pintype "passive"))
    )
    (net (code "47") (name "/SD_CS") (class "Default")
      (node (ref "LPC1") (pin "8") (pinfunction "8_8") (pintype "passive"))
      (node (ref "R8") (pin "1") (pinfunction "1_1") (pintype "passive"))
      (node (ref "U1") (pin "2") (pinfunction "CS_2") (pintype "bidirectional"))
    )
    (net (code "48") (name "/SD_IRQ") (class "Default")
      (node (ref "JP6") (pin "1") (pinfunction "1_1") (pintype "passive"))
      (node (ref "LPC1") (pin "61") (pinfunction "61_61") (pintype "passive"))
    )
    (net (code "49") (name "/SD_MISO") (class "Default")
      (node (ref "LPC1") (pin "6") (pinfunction "6_6") (pintype "passive"))
      (node (ref "R9") (pin "1") (pinfunction "1_1") (pintype "passive"))
      (node (ref "U1") (pin "7") (pinfunction "DO_7") (pintype "bidirectional"))
    )
    (net (code "50") (name "/SD_MOSI") (class "Default")
      (node (ref "LPC1") (pin "5") (pinfunction "5_5") (pintype "passive"))
      (node (ref "R10") (pin "1") (pinfunction "1_1") (pintype "passive"))
      (node (ref "U1") (pin "3") (pinfunction "DI_3") (pintype "bidirectional"))
    )
    (net (code "51") (name "/SD_SCK") (class "Default")
      (node (ref "LPC1") (pin "7") (pinfunction "7_7") (pintype "passive"))
      (node (ref "U1") (pin "5") (pinfunction "SCK_5") (pintype "bidirectional"))
    )
    (net (code "52") (name "/SD_WP") (class "Default")
      (node (ref "JP6") (pin "2") (pinfunction "2_2") (pintype "passive"))
      (node (ref "LPC1") (pin "60") (pinfunction "60_60") (pintype "passive"))
    )
    (net (code "53") (name "/SMALL_MOSFET_POWER") (class "Default")
      (node (ref "C1") (pin "A") (pinfunction "+_A") (pintype "passive"))
      (node (ref "R2") (pin "1") (pinfunction "1_1") (pintype "passive"))
      (node (ref "X1") (pin "1") (pinfunction "SK_1") (pintype "passive"))
      (node (ref "X3") (pin "1") (pinfunction "SK_1") (pintype "passive"))
    )
    (net (code "54") (name "/SSEL1") (class "Default")
      (node (ref "JP11") (pin "5") (pinfunction "5_5") (pintype "passive"))
      (node (ref "LPC1") (pin "14") (pinfunction "14_14") (pintype "passive"))
    )
    (net (code "55") (name "/STP1") (class "Default")
      (node (ref "LPC1") (pin "42") (pinfunction "42_42") (pintype "passive"))
      (node (ref "M4") (pin "15") (pinfunction "STEP_15") (pintype "input"))
    )
    (net (code "56") (name "/STP2") (class "Default")
      (node (ref "LPC1") (pin "43") (pinfunction "43_43") (pintype "passive"))
      (node (ref "M3") (pin "15") (pinfunction "STEP_15") (pintype "input"))
    )
    (net (code "57") (name "/STP3") (class "Default")
      (node (ref "JP16") (pin "2") (pinfunction "2_2") (pintype "passive"))
      (node (ref "LPC1") (pin "44") (pinfunction "44_44") (pintype "passive"))
    )
    (net (code "58") (name "/STP4") (class "Default")
      (node (ref "LPC1") (pin "45") (pinfunction "45_45") (pintype "passive"))
      (node (ref "M2") (pin "15") (pinfunction "STEP_15") (pintype "input"))
    )
    (net (code "59") (name "/STP5") (class "Default")
      (node (ref "LPC1") (pin "50") (pinfunction "50_50") (pintype "passive"))
      (node (ref "M1") (pin "15") (pinfunction "STEP_15") (pintype "input"))
    )
    (net (code "60") (name "/TD+") (class "Default")
      (node (ref "LPC1") (pin "35") (pinfunction "35_35") (pintype "passive"))
      (node (ref "RJ1") (pin "TD+") (pinfunction "TD+_TD+") (pintype "bidirectional"))
    )
    (net (code "61") (name "/TD-") (class "Default")
      (node (ref "LPC1") (pin "34") (pinfunction "34_34") (pintype "passive"))
      (node (ref "RJ1") (pin "TD-") (pinfunction "TD-_TD-") (pintype "bidirectional"))
    )
    (net (code "62") (name "/TH1") (class "Default")
      (node (ref "C2") (pin "A") (pinfunction "+_A") (pintype "passive"))
      (node (ref "LPC1") (pin "15") (pinfunction "15_15") (pintype "passive"))
      (node (ref "RN1") (pin "1") (pinfunction "1_1") (pintype "passive"))
      (node (ref "THERM.") (pin "2") (pinfunction "2_2") (pintype "passive"))
    )
    (net (code "63") (name "/TH2") (class "Default")
      (node (ref "C3") (pin "A") (pinfunction "+_A") (pintype "passive"))
      (node (ref "LPC1") (pin "16") (pinfunction "16_16") (pintype "passive"))
      (node (ref "RN1") (pin "2") (pinfunction "1_2") (pintype "passive"))
      (node (ref "THERM.") (pin "4") (pinfunction "4_4") (pintype "passive"))
    )
    (net (code "64") (name "/TH3") (class "Default")
      (node (ref "C4") (pin "A") (pinfunction "+_A") (pintype "passive"))
      (node (ref "LPC1") (pin "17") (pinfunction "17_17") (pintype "passive"))
      (node (ref "RN1") (pin "3") (pinfunction "1_3") (pintype "passive"))
      (node (ref "THERM.") (pin "6") (pinfunction "6_6") (pintype "passive"))
    )
    (net (code "65") (name "/TH4") (class "Default")
      (node (ref "C5") (pin "A") (pinfunction "+_A") (pintype "passive"))
      (node (ref "LPC1") (pin "18") (pinfunction "18_18") (pintype "passive"))
      (node (ref "RN1") (pin "4") (pinfunction "1_4") (pintype "passive"))
      (node (ref "THERM.") (pin "8") (pinfunction "8_8") (pintype "passive"))
    )
    (net (code "66") (name "/TX_0") (class "Default")
      (node (ref "JP5") (pin "3") (pinfunction "3_3") (pintype "passive"))
      (node (ref "LPC1") (pin "21") (pinfunction "21_21") (pintype "passive"))
    )
    (net (code "67") (name "/USB_D+") (class "Default")
      (node (ref "C14") (pin "2") (pinfunction "2_2") (pintype "passive"))
      (node (ref "LPC1") (pin "37") (pinfunction "37_37") (pintype "passive"))
      (node (ref "R17") (pin "1") (pinfunction "1_1") (pintype "passive"))
      (node (ref "R20") (pin "2") (pinfunction "2_2") (pintype "passive"))
    )
    (net (code "68") (name "/USB_D-") (class "Default")
      (node (ref "C13") (pin "2") (pinfunction "2_2") (pintype "passive"))
      (node (ref "LPC1") (pin "36") (pinfunction "36_36") (pintype "passive"))
      (node (ref "R21") (pin "2") (pinfunction "2_2") (pintype "passive"))
    )
    (net (code "69") (name "/VBB") (class "Default")
      (node (ref "C12") (pin "+") (pinfunction "+_+") (pintype "passive"))
      (node (ref "C21") (pin "+") (pinfunction "+_+") (pintype "passive"))
      (node (ref "C25") (pin "+") (pinfunction "+_+") (pintype "passive"))
      (node (ref "C26") (pin "+") (pinfunction "+_+") (pintype "passive"))
      (node (ref "D3") (pin "C") (pinfunction "C_C") (pintype "passive"))
      (node (ref "M1") (pin "8") (pinfunction "VMOT_8") (pintype "power_in"))
      (node (ref "M2") (pin "8") (pinfunction "VMOT_8") (pintype "power_in"))
      (node (ref "M3") (pin "8") (pinfunction "VMOT_8") (pintype "power_in"))
      (node (ref "M4") (pin "8") (pinfunction "VMOT_8") (pintype "power_in"))
      (node (ref "Q5") (pin "S") (pinfunction "S_S") (pintype "passive"))
      (node (ref "R54") (pin "2") (pinfunction "2_2") (pintype "passive"))
    )
    (net (code "70") (name "/VBB_IN") (class "Default")
      (node (ref "Q5") (pin "D") (pinfunction "D_D") (pintype "passive"))
      (node (ref "X7") (pin "2") (pinfunction "SK_2") (pintype "passive"))
    )
    (net (code "71") (name "/X_MAX") (class "Default")
      (node (ref "C16") (pin "1") (pinfunction "1_1") (pintype "passive"))
      (node (ref "LPC1") (pin "66") (pinfunction "66_66") (pintype "passive"))
      (node (ref "R25") (pin "2") (pinfunction "2_2") (pintype "passive"))
    )
    (net (code "72") (name "/X_MIN") (class "Default")
      (node (ref "C15") (pin "1") (pinfunction "1_1") (pintype "passive"))
      (node (ref "LPC1") (pin "67") (pinfunction "67_67") (pintype "passive"))
      (node (ref "R22") (pin "2") (pinfunction "2_2") (pintype "passive"))
    )
    (net (code "73") (name "/Y_MAX") (class "Default")
      (node (ref "C18") (pin "1") (pinfunction "1_1") (pintype "passive"))
      (node (ref "LPC1") (pin "64") (pinfunction "64_64") (pintype "passive"))
      (node (ref "R36") (pin "2") (pinfunction "2_2") (pintype "passive"))
    )
    (net (code "74") (name "/Y_MIN") (class "Default")
      (node (ref "C17") (pin "1") (pinfunction "1_1") (pintype "passive"))
      (node (ref "LPC1") (pin "65") (pinfunction "65_65") (pintype "passive"))
      (node (ref "R28") (pin "2") (pinfunction "2_2") (pintype "passive"))
    )
    (net (code "75") (name "/Z_MAX") (class "Default")
      (node (ref "C20") (pin "1") (pinfunction "1_1") (pintype "passive"))
      (node (ref "LPC1") (pin "62") (pinfunction "62_62") (pintype "passive"))
      (node (ref "R45") (pin "2") (pinfunction "2_2") (pintype "passive"))
    )
    (net (code "76") (name "/Z_MIN") (class "Default")
      (node (ref "C19") (pin "1") (pinfunction "1_1") (pintype "passive"))
      (node (ref "LPC1") (pin "63") (pinfunction "63_63") (pintype "passive"))
      (node (ref "R43") (pin "2") (pinfunction "2_2") (pintype "passive"))
    )
    (net (code "77") (name "3.3V") (class "Default")
      (node (ref "C7") (pin "2") (pinfunction "2_2") (pintype "passive"))
      (node (ref "C8") (pin "2") (pinfunction "2_2") (pintype "passive"))
      (node (ref "C9") (pin "A") (pinfunction "+_A") (pintype "passive"))
      (node (ref "D1") (pin "C") (pinfunction "C_C") (pintype "passive"))
      (node (ref "FB1") (pin "2") (pinfunction "P$2_2") (pintype "bidirectional"))
      (node (ref "JP11") (pin "6") (pinfunction "6_6") (pintype "passive"))
      (node (ref "JP12") (pin "1") (pinfunction "1_1") (pintype "passive"))
      (node (ref "JP13") (pin "1") (pinfunction "1_1") (pintype "passive"))
      (node (ref "JP7") (pin "1") (pinfunction "1_1") (pintype "passive"))
      (node (ref "JP9") (pin "1") (pinfunction "1_1") (pintype "passive"))
      (node (ref "L1") (pin "2") (pinfunction "2_2") (pintype "passive"))
      (node (ref "LPC1") (pin "28") (pinfunction "28_28") (pintype "passive"))
      (node (ref "MS1") (pin "2") (pinfunction "2_2") (pintype "passive"))
      (node (ref "MS2") (pin "2") (pinfunction "2_2") (pintype "passive"))
      (node (ref "MS3") (pin "2") (pinfunction "2_2") (pintype "passive"))
      (node (ref "Q2") (pin "2") (pinfunction "S_2") (pintype "passive"))
      (node (ref "R10") (pin "2") (pinfunction "2_2") (pintype "passive"))
      (node (ref "R11") (pin "2") (pinfunction "2_2") (pintype "passive"))
      (node (ref "R12") (pin "2") (pinfunction "2_2") (pintype "passive"))
      (node (ref "R30") (pin "2") (pinfunction "2_2") (pintype "passive"))
      (node (ref "R31") (pin "2") (pinfunction "2_2") (pintype "passive"))
      (node (ref "R32") (pin "2") (pinfunction "2_2") (pintype "passive"))
      (node (ref "R33") (pin "2") (pinfunction "2_2") (pintype "passive"))
      (node (ref "R38") (pin "2") (pinfunction "2_2") (pintype "passive"))
      (node (ref "R39") (pin "2") (pinfunction "2_2") (pintype "passive"))
      (node (ref "R46") (pin "2") (pinfunction "2_2") (pintype "passive"))
      (node (ref "R47") (pin "2") (pinfunction "2_2") (pintype "passive"))
      (node (ref "R48") (pin "2") (pinfunction "2_2") (pintype "passive"))
      (node (ref "R49") (pin "2") (pinfunction "2_2") (pintype "passive"))
      (node (ref "R50") (pin "2") (pinfunction "2_2") (pintype "passive"))
      (node (ref "R8") (pin "2") (pinfunction "2_2") (pintype "passive"))
      (node (ref "R9") (pin "2") (pinfunction "2_2") (pintype "passive"))
      (node (ref "SJ1") (pin "1") (pinfunction "1_1") (pintype "passive"))
      (node (ref "U1") (pin "4") (pinfunction "VCC_4") (pintype "bidirectional"))
      (node (ref "X2") (pin "1") (pinfunction "S_1") (pintype "passive"))
      (node (ref "X2") (pin "11") (pinfunction "S_11") (pintype "passive"))
      (node (ref "X2") (pin "2") (pinfunction "S_2") (pintype "passive"))
    )
    (net (code "78") (name "5V") (class "Default")
      (node (ref "JP13") (pin "3") (pinfunction "3_3") (pintype "passive"))
      (node (ref "JP7") (pin "3") (pinfunction "3_3") (pintype "passive"))
      (node (ref "LPC1") (pin "2") (pinfunction "2_2") (pintype "passive"))
      (node (ref "SJ1") (pin "3") (pinfunction "3_3") (pintype "passive"))
    )
    (net (code "79") (name "GND") (class "Default")
      (node (ref "ATX") (pin "C") (pinfunction "C_C") (pintype "passive"))
      (node (ref "C1") (pin "C") (pinfunction "-_C") (pintype "passive"))
      (node (ref "C10") (pin "-") (pinfunction "-_-") (pintype "passive"))
      (node (ref "C11") (pin "1") (pinfunction "1_1") (pintype "passive"))
      (node (ref "C12") (pin "-") (pinfunction "-_-") (pintype "passive"))
      (node (ref "C13") (pin "1") (pinfunction "1_1") (pintype "passive"))
      (node (ref "C14") (pin "1") (pinfunction "1_1") (pintype "passive"))
      (node (ref "C15") (pin "2") (pinfunction "2_2") (pintype "passive"))
      (node (ref "C16") (pin "2") (pinfunction "2_2") (pintype "passive"))
      (node (ref "C17") (pin "2") (pinfunction "2_2") (pintype "passive"))
      (node (ref "C18") (pin "2") (pinfunction "2_2") (pintype "passive"))
      (node (ref "C19") (pin "2") (pinfunction "2_2") (pintype "passive"))
      (node (ref "C2") (pin "C") (pinfunction "-_C") (pintype "passive"))
      (node (ref "C20") (pin "2") (pinfunction "2_2") (pintype "passive"))
      (node (ref "C21") (pin "-") (pinfunction "-_-") (pintype "passive"))
      (node (ref "C22") (pin "2") (pinfunction "2_2") (pintype "passive"))
      (node (ref "C23") (pin "C") (pinfunction "-_C") (pintype "passive"))
      (node (ref "C24") (pin "1") (pinfunction "1_1") (pintype "passive"))
      (node (ref "C25") (pin "-") (pinfunction "-_-") (pintype "passive"))
      (node (ref "C26") (pin "-") (pinfunction "-_-") (pintype "passive"))
      (node (ref "C3") (pin "C") (pinfunction "-_C") (pintype "passive"))
      (node (ref "C4") (pin "C") (pinfunction "-_C") (pintype "passive"))
      (node (ref "C5") (pin "C") (pinfunction "-_C") (pintype "passive"))
      (node (ref "C6") (pin "1") (pinfunction "1_1") (pintype "passive"))
      (node (ref "C7") (pin "1") (pinfunction "1_1") (pintype "passive"))
      (node (ref "C8") (pin "1") (pinfunction "1_1") (pintype "passive"))
      (node (ref "C9") (pin "C") (pinfunction "-_C") (pintype "passive"))
      (node (ref "D2") (pin "A") (pinfunction "A_A") (pintype "passive"))
      (node (ref "FLOW") (pin "2") (pinfunction "S_2") (pintype "passive"))
      (node (ref "IC1") (pin "3") (pinfunction "GND_3") (pintype "power_in"))
      (node (ref "IC2") (pin "3") (pinfunction "P$2_3") (pintype "bidirectional"))
      (node (ref "JP10") (pin "5") (pinfunction "5_5") (pintype "passive"))
      (node (ref "JP11") (pin "1") (pinfunction "1_1") (pintype "passive"))
      (node (ref "JP12") (pin "2") (pinfunction "2_2") (pintype "passive"))
      (node (ref "JP14") (pin "2") (pinfunction "2_2") (pintype "passive"))
      (node (ref "JP16") (pin "4") (pinfunction "4_4") (pintype "passive"))
      (node (ref "JP5") (pin "1") (pinfunction "1_1") (pintype "passive"))
      (node (ref "JP7") (pin "2") (pinfunction "2_2") (pintype "passive"))
      (node (ref "JP8") (pin "5") (pinfunction "5_5") (pintype "passive"))
      (node (ref "JP9") (pin "2") (pinfunction "2_2") (pintype "passive"))
      (node (ref "LED1") (pin "C") (pinfunction "C_C") (pintype "passive"))
      (node (ref "LED2") (pin "C") (pinfunction "C_C") (pintype "passive"))
      (node (ref "LED3") (pin "C") (pinfunction "C_C") (pintype "passive"))
      (node (ref "LED4") (pin "C") (pinfunction "C_C") (pintype "passive"))
      (node (ref "LEDS") (pin "2") (pinfunction "2_2") (pintype "passive"))
      (node (ref "LEDS") (pin "4") (pinfunction "4_4") (pintype "passive"))
      (node (ref "LEDS") (pin "6") (pinfunction "6_6") (pintype "passive"))
      (node (ref "LEDS") (pin "8") (pinfunction "8_8") (pintype "passive"))
      (node (ref "LPC1") (pin "1") (pinfunction "1_1") (pintype "passive"))
      (node (ref "LPC1") (pin "54") (pinfunction "54_54") (pintype "passive"))
      (node (ref "M1") (pin "1") (pinfunction "GND_1") (pintype "power_in"))
      (node (ref "M1") (pin "7") (pinfunction "GND_7") (pintype "power_in"))
      (node (ref "M2") (pin "1") (pinfunction "GND_1") (pintype "power_in"))
      (node (ref "M2") (pin "7") (pinfunction "GND_7") (pintype "power_in"))
      (node (ref "M3") (pin "1") (pinfunction "GND_1") (pintype "power_in"))
      (node (ref "M3") (pin "7") (pinfunction "GND_7") (pintype "power_in"))
      (node (ref "M4") (pin "1") (pinfunction "GND_1") (pintype "power_in"))
      (node (ref "M4") (pin "7") (pinfunction "GND_7") (pintype "power_in"))
      (node (ref "PS_ON") (pin "2") (pinfunction "2_2") (pintype "passive"))
      (node (ref "Q1") (pin "3") (pinfunction "S_3") (pintype "passive"))
      (node (ref "Q3") (pin "S") (pinfunction "S_S") (pintype "passive"))
      (node (ref "Q4") (pin "3") (pinfunction "S_3") (pintype "passive"))
      (node (ref "R15") (pin "1") (pinfunction "1_1") (pintype "passive"))
      (node (ref "R16") (pin "1") (pinfunction "1_1") (pintype "passive"))
      (node (ref "R23") (pin "2") (pinfunction "2_2") (pintype "passive"))
      (node (ref "R5") (pin "1") (pinfunction "1_1") (pintype "passive"))
      (node (ref "R53") (pin "2") (pinfunction "2_2") (pintype "passive"))
      (node (ref "R55") (pin "2") (pinfunction "2_2") (pintype "passive"))
      (node (ref "R7") (pin "2") (pinfunction "2_2") (pintype "passive"))
      (node (ref "RESET") (pin "3") (pinfunction "3_3") (pintype "passive"))
      (node (ref "RESET") (pin "4") (pinfunction "4_4") (pintype "passive"))
      (node (ref "RJ1") (pin "G+") (pinfunction "G+_G+") (pintype "bidirectional"))
      (node (ref "RJ1") (pin "G-") (pinfunction "G-_G-") (pintype "bidirectional"))
      (node (ref "RJ1") (pin "GND") (pinfunction "GND_GND") (pintype "bidirectional"))
      (node (ref "RJ1") (pin "SHIELD0") (pinfunction "SHIELD0_SHIELD0") (pintype "bidirectional"))
      (node (ref "RJ1") (pin "SHIELD1") (pinfunction "SHIELD1_SHIELD1") (pintype "bidirectional"))
      (node (ref "RJ1") (pin "Y+") (pinfunction "Y+_Y+") (pintype "bidirectional"))
      (node (ref "RJ1") (pin "Y-") (pinfunction "Y-_Y-") (pintype "bidirectional"))
      (node (ref "S1") (pin "3") (pinfunction "3_3") (pintype "passive"))
      (node (ref "S1") (pin "4") (pinfunction "4_4") (pintype "passive"))
      (node (ref "S2") (pin "3") (pinfunction "3_3") (pintype "passive"))
      (node (ref "S2") (pin "4") (pinfunction "4_4") (pintype "passive"))
      (node (ref "THERM.") (pin "1") (pinfunction "1_1") (pintype "passive"))
      (node (ref "THERM.") (pin "3") (pinfunction "3_3") (pintype "passive"))
      (node (ref "THERM.") (pin "5") (pinfunction "5_5") (pintype "passive"))
      (node (ref "THERM.") (pin "7") (pinfunction "7_7") (pintype "passive"))
      (node (ref "U1") (pin "6") (pinfunction "GND_6") (pintype "bidirectional"))
      (node (ref "U1") (pin "CD1") (pinfunction "SHIELD_CD1") (pintype "bidirectional"))
      (node (ref "U1") (pin "CD2") (pinfunction "SHIELD_CD2") (pintype "bidirectional"))
      (node (ref "U1") (pin "GND1") (pinfunction "SHIELD_GND1") (pintype "bidirectional"))
      (node (ref "U1") (pin "GND3") (pinfunction "SHIELD_GND3") (pintype "bidirectional"))
      (node (ref "USB") (pin "C") (pinfunction "C_C") (pintype "passive"))
      (node (ref "VBB") (pin "C") (pinfunction "C_C") (pintype "passive"))
      (node (ref "X1") (pin "2") (pinfunction "SK_2") (pintype "passive"))
      (node (ref "X2") (pin "13") (pinfunction "S_13") (pintype "passive"))
      (node (ref "X2") (pin "15") (pinfunction "S_15") (pintype "passive"))
      (node (ref "X2") (pin "16") (pinfunction "S_16") (pintype "passive"))
      (node (ref "X2") (pin "17") (pinfunction "S_17") (pintype "passive"))
      (node (ref "X2") (pin "3") (pinfunction "S_3") (pintype "passive"))
      (node (ref "X2") (pin "5") (pinfunction "S_5") (pintype "passive"))
      (node (ref "X2") (pin "7") (pinfunction "S_7") (pintype "passive"))
      (node (ref "X4") (pin "2") (pinfunction "SK_2") (pintype "passive"))
      (node (ref "X6") (pin "GND") (pinfunction "GND_GND") (pintype "bidirectional"))
      (node (ref "X7") (pin "1") (pinfunction "SK_1") (pintype "passive"))
      (node (ref "XMAX") (pin "2") (pinfunction "2_2") (pintype "passive"))
      (node (ref "XMIN") (pin "2") (pinfunction "2_2") (pintype "passive"))
      (node (ref "YMAX") (pin "2") (pinfunction "2_2") (pintype "passive"))
      (node (ref "YMIN") (pin "2") (pinfunction "2_2") (pintype "passive"))
      (node (ref "ZMAX") (pin "2") (pinfunction "2_2") (pintype "passive"))
      (node (ref "ZMIN") (pin "2") (pinfunction "2_2") (pintype "passive"))
    )
    (net (code "80") (name "Net-(ATX-PadA)") (class "Default")
      (node (ref "ATX") (pin "A") (pinfunction "A_A") (pintype "passive"))
      (node (ref "R3") (pin "1") (pinfunction "1_1") (pintype "passive"))
    )
    (net (code "81") (name "Net-(BIG-PadA)") (class "Default")
      (node (ref "BIG") (pin "A") (pinfunction "A_A") (pintype "passive"))
      (node (ref "R13") (pin "2") (pinfunction "2_2") (pintype "passive"))
    )
    (net (code "82") (name "Net-(D3-PadA)") (class "Default")
      (node (ref "D3") (pin "A") (pinfunction "A_A") (pintype "passive"))
      (node (ref "Q5") (pin "G") (pinfunction "G_G") (pintype "passive"))
      (node (ref "R55") (pin "1") (pinfunction "1_1") (pintype "passive"))
    )
    (net (code "83") (name "Net-(FAN-PadA)") (class "Default")
      (node (ref "FAN") (pin "A") (pinfunction "A_A") (pintype "passive"))
      (node (ref "R51") (pin "2") (pinfunction "2_2") (pintype "passive"))
    )
    (net (code "84") (name "Net-(FB1-P$1)") (class "Default")
      (node (ref "C24") (pin "2") (pinfunction "2_2") (pintype "passive"))
      (node (ref "FB1") (pin "1") (pinfunction "P$1_1") (pintype "bidirectional"))
      (node (ref "RJ1") (pin "P4") (pinfunction "P4_P4") (pintype "bidirectional"))
      (node (ref "RJ1") (pin "P5") (pinfunction "P5_P5") (pintype "bidirectional"))
    )
    (net (code "85") (name "Net-(IC1A-I)") (class "Default")
      (node (ref "IC1") (pin "2") (pinfunction "I_2") (pintype "input"))
      (node (ref "X2") (pin "8") (pinfunction "S_8") (pintype "passive"))
    )
    (net (code "86") (name "Net-(IC1A-O)") (class "Default")
      (node (ref "IC1") (pin "4") (pinfunction "O_4") (pintype "open_collector"))
      (node (ref "R1") (pin "2") (pinfunction "2_2") (pintype "passive"))
    )
    (net (code "87") (name "Net-(IC1B-VCC)") (class "Default")
      (node (ref "C6") (pin "2") (pinfunction "2_2") (pintype "passive"))
      (node (ref "IC1") (pin "5") (pinfunction "VCC_5") (pintype "power_in"))
      (node (ref "R3") (pin "2") (pinfunction "2_2") (pintype "passive"))
      (node (ref "X2") (pin "9") (pinfunction "S_9") (pintype "passive"))
    )
    (net (code "88") (name "Net-(IC2A-P$2)") (class "Default")
      (node (ref "IC2") (pin "7") (pinfunction "P$2_7") (pintype "bidirectional"))
      (node (ref "R14") (pin "1") (pinfunction "1_1") (pintype "passive"))
    )
    (net (code "89") (name "Net-(IC2B-P$1)") (class "Default")
      (node (ref "IC2") (pin "4") (pinfunction "P$1_4") (pintype "bidirectional"))
      (node (ref "R15") (pin "2") (pinfunction "2_2") (pintype "passive"))
    )
    (net (code "90") (name "Net-(J4A-S)") (class "Default")
      (node (ref "FAN") (pin "C") (pinfunction "C_C") (pintype "passive"))
      (node (ref "J4") (pin "1") (pinfunction "S_1") (pintype "passive"))
      (node (ref "Q4") (pin "4") (pinfunction "D_4") (pintype "passive"))
    )
    (net (code "91") (name "Net-(JP5-Pad2)") (class "Default")
      (node (ref "JP5") (pin "2") (pinfunction "2_2") (pintype "passive"))
      (node (ref "R4") (pin "1") (pinfunction "1_1") (pintype "passive"))
      (node (ref "R5") (pin "2") (pinfunction "2_2") (pintype "passive"))
    )
    (net (code "92") (name "Net-(JP7-Pad4)") (class "Default")
      (node (ref "JP7") (pin "4") (pinfunction "4_4") (pintype "passive"))
      (node (ref "LPC1") (pin "3") (pinfunction "3_3") (pintype "passive"))
    )
    (net (code "93") (name "Net-(JP13-Pad2)") (class "Default")
      (node (ref "JP13") (pin "2") (pinfunction "2_2") (pintype "passive"))
      (node (ref "R19") (pin "2") (pinfunction "2_2") (pintype "passive"))
      (node (ref "R24") (pin "2") (pinfunction "2_2") (pintype "passive"))
      (node (ref "R27") (pin "2") (pinfunction "2_2") (pintype "passive"))
      (node (ref "R34") (pin "2") (pinfunction "2_2") (pintype "passive"))
      (node (ref "R40") (pin "2") (pinfunction "2_2") (pintype "passive"))
      (node (ref "R44") (pin "2") (pinfunction "2_2") (pintype "passive"))
      (node (ref "XMAX") (pin "3") (pinfunction "3_3") (pintype "passive"))
      (node (ref "XMIN") (pin "3") (pinfunction "3_3") (pintype "passive"))
      (node (ref "YMAX") (pin "3") (pinfunction "3_3") (pintype "passive"))
      (node (ref "YMIN") (pin "3") (pinfunction "3_3") (pintype "passive"))
      (node (ref "ZMAX") (pin "3") (pinfunction "3_3") (pintype "passive"))
      (node (ref "ZMIN") (pin "3") (pinfunction "3_3") (pintype "passive"))
    )
    (net (code "94") (name "Net-(JP15-Pad1)") (class "Default")
      (node (ref "JP15") (pin "1") (pinfunction "1_1") (pintype "passive"))
      (node (ref "PLAY") (pin "C") (pinfunction "C_C") (pintype "passive"))
      (node (ref "R33") (pin "1") (pinfunction "1_1") (pintype "passive"))
    )
    (net (code "95") (name "Net-(LED1-PadA)") (class "Default")
      (node (ref "LED1") (pin "A") (pinfunction "A_A") (pintype "passive"))
      (node (ref "R26") (pin "1") (pinfunction "1_1") (pintype "passive"))
    )
    (net (code "96") (name "Net-(LED2-PadA)") (class "Default")
      (node (ref "LED2") (pin "A") (pinfunction "A_A") (pintype "passive"))
      (node (ref "R29") (pin "1") (pinfunction "1_1") (pintype "passive"))
    )
    (net (code "97") (name "Net-(LED3-PadA)") (class "Default")
      (node (ref "LED3") (pin "A") (pinfunction "A_A") (pintype "passive"))
      (node (ref "R35") (pin "1") (pinfunction "1_1") (pintype "passive"))
    )
    (net (code "98") (name "Net-(LED4-PadA)") (class "Default")
      (node (ref "LED4") (pin "A") (pinfunction "A_A") (pintype "passive"))
      (node (ref "R37") (pin "1") (pinfunction "1_1") (pintype "passive"))
    )
    (net (code "99") (name "Net-(M1-A1)") (class "Default")
      (node (ref "M1") (pin "4") (pinfunction "A1_4") (pintype "output"))
      (node (ref "STEPPER1") (pin "2") (pinfunction "S_2") (pintype "passive"))
    )
    (net (code "100") (name "Net-(M1-A2)") (class "Default")
      (node (ref "M1") (pin "3") (pinfunction "A2_3") (pintype "output"))
      (node (ref "STEPPER1") (pin "1") (pinfunction "S_1") (pintype "passive"))
    )
    (net (code "101") (name "Net-(M1-B1)") (class "Default")
      (node (ref "M1") (pin "5") (pinfunction "B1_5") (pintype "output"))
      (node (ref "STEPPER1") (pin "3") (pinfunction "S_3") (pintype "passive"))
    )
    (net (code "102") (name "Net-(M1-B2)") (class "Default")
      (node (ref "M1") (pin "6") (pinfunction "B2_6") (pintype "output"))
      (node (ref "STEPPER1") (pin "4") (pinfunction "S_4") (pintype "passive"))
    )
    (net (code "103") (name "Net-(M1-{slash}RESET)") (class "Default")
      (node (ref "M1") (pin "13") (pinfunction "/RESET_13") (pintype "input"))
      (node (ref "R12") (pin "1") (pinfunction "1_1") (pintype "passive"))
    )
    (net (code "104") (name "Net-(M1-{slash}SLEEP)") (class "Default")
      (node (ref "M1") (pin "14") (pinfunction "/SLEEP_14") (pintype "input"))
      (node (ref "R11") (pin "1") (pinfunction "1_1") (pintype "passive"))
    )
    (net (code "105") (name "Net-(M2-A1)") (class "Default")
      (node (ref "M2") (pin "4") (pinfunction "A1_4") (pintype "output"))
      (node (ref "STEPPER2") (pin "2") (pinfunction "S_2") (pintype "passive"))
    )
    (net (code "106") (name "Net-(M2-A2)") (class "Default")
      (node (ref "M2") (pin "3") (pinfunction "A2_3") (pintype "output"))
      (node (ref "STEPPER2") (pin "1") (pinfunction "S_1") (pintype "passive"))
    )
    (net (code "107") (name "Net-(M2-B1)") (class "Default")
      (node (ref "M2") (pin "5") (pinfunction "B1_5") (pintype "output"))
      (node (ref "STEPPER2") (pin "3") (pinfunction "S_3") (pintype "passive"))
    )
    (net (code "108") (name "Net-(M2-B2)") (class "Default")
      (node (ref "M2") (pin "6") (pinfunction "B2_6") (pintype "output"))
      (node (ref "STEPPER2") (pin "4") (pinfunction "S_4") (pintype "passive"))
    )
    (net (code "109") (name "Net-(M2-{slash}RESET)") (class "Default")
      (node (ref "M2") (pin "13") (pinfunction "/RESET_13") (pintype "input"))
      (node (ref "R39") (pin "1") (pinfunction "1_1") (pintype "passive"))
    )
    (net (code "110") (name "Net-(M2-{slash}SLEEP)") (class "Default")
      (node (ref "M2") (pin "14") (pinfunction "/SLEEP_14") (pintype "input"))
      (node (ref "R38") (pin "1") (pinfunction "1_1") (pintype "passive"))
    )
    (net (code "111") (name "Net-(M3-A1)") (class "Default")
      (node (ref "M3") (pin "4") (pinfunction "A1_4") (pintype "output"))
      (node (ref "STEPPER3") (pin "2") (pinfunction "S_2") (pintype "passive"))
    )
    (net (code "112") (name "Net-(M3-A2)") (class "Default")
      (node (ref "M3") (pin "3") (pinfunction "A2_3") (pintype "output"))
      (node (ref "STEPPER3") (pin "1") (pinfunction "S_1") (pintype "passive"))
    )
    (net (code "113") (name "Net-(M3-B1)") (class "Default")
      (node (ref "M3") (pin "5") (pinfunction "B1_5") (pintype "output"))
      (node (ref "STEPPER3") (pin "3") (pinfunction "S_3") (pintype "passive"))
    )
    (net (code "114") (name "Net-(M3-B2)") (class "Default")
      (node (ref "M3") (pin "6") (pinfunction "B2_6") (pintype "output"))
      (node (ref "STEPPER3") (pin "4") (pinfunction "S_4") (pintype "passive"))
    )
    (net (code "115") (name "Net-(M3-{slash}RESET)") (class "Default")
      (node (ref "M3") (pin "13") (pinfunction "/RESET_13") (pintype "input"))
      (node (ref "R48") (pin "1") (pinfunction "1_1") (pintype "passive"))
    )
    (net (code "116") (name "Net-(M3-{slash}SLEEP)") (class "Default")
      (node (ref "M3") (pin "14") (pinfunction "/SLEEP_14") (pintype "input"))
      (node (ref "R47") (pin "1") (pinfunction "1_1") (pintype "passive"))
    )
    (net (code "117") (name "Net-(M4-A1)") (class "Default")
      (node (ref "M4") (pin "4") (pinfunction "A1_4") (pintype "output"))
      (node (ref "STEPPER4") (pin "2") (pinfunction "S_2") (pintype "passive"))
    )
    (net (code "118") (name "Net-(M4-A2)") (class "Default")
      (node (ref "M4") (pin "3") (pinfunction "A2_3") (pintype "output"))
      (node (ref "STEPPER4") (pin "1") (pinfunction "S_1") (pintype "passive"))
    )
    (net (code "119") (name "Net-(M4-B1)") (class "Default")
      (node (ref "M4") (pin "5") (pinfunction "B1_5") (pintype "output"))
      (node (ref "STEPPER4") (pin "3") (pinfunction "S_3") (pintype "passive"))
    )
    (net (code "120") (name "Net-(M4-B2)") (class "Default")
      (node (ref "M4") (pin "6") (pinfunction "B2_6") (pintype "output"))
      (node (ref "STEPPER4") (pin "4") (pinfunction "S_4") (pintype "passive"))
    )
    (net (code "121") (name "Net-(M4-{slash}RESET)") (class "Default")
      (node (ref "M4") (pin "13") (pinfunction "/RESET_13") (pintype "input"))
      (node (ref "R50") (pin "1") (pinfunction "1_1") (pintype "passive"))
    )
    (net (code "122") (name "Net-(M4-{slash}SLEEP)") (class "Default")
      (node (ref "M4") (pin "14") (pinfunction "/SLEEP_14") (pintype "input"))
      (node (ref "R49") (pin "1") (pinfunction "1_1") (pintype "passive"))
    )
    (net (code "123") (name "Net-(Q1-D)") (class "Default")
      (node (ref "Q1") (pin "4") (pinfunction "D_4") (pintype "passive"))
      (node (ref "SMALL") (pin "C") (pinfunction "C_C") (pintype "passive"))
      (node (ref "X3") (pin "2") (pinfunction "SK_2") (pintype "passive"))
    )
    (net (code "124") (name "Net-(Q1-G)") (class "Default")
      (node (ref "Q1") (pin "1") (pinfunction "G_1") (pintype "passive"))
      (node (ref "R6") (pin "1") (pinfunction "1_1") (pintype "passive"))
    )
    (net (code "125") (name "Net-(Q2-D)") (class "Default")
      (node (ref "Q2") (pin "3") (pinfunction "D_3") (pintype "passive"))
      (node (ref "R17") (pin "2") (pinfunction "2_2") (pintype "passive"))
    )
    (net (code "126") (name "Net-(Q4-G)") (class "Default")
      (node (ref "Q4") (pin "1") (pinfunction "G_1") (pintype "passive"))
      (node (ref "R52") (pin "1") (pinfunction "1_1") (pintype "passive"))
    )
    (net (code "127") (name "Net-(R2-Pad2)") (class "Default")
      (node (ref "R2") (pin "2") (pinfunction "2_2") (pintype "passive"))
      (node (ref "SMALL") (pin "A") (pinfunction "A_A") (pintype "passive"))
    )
    (net (code "128") (name "Net-(R18-Pad1)") (class "Default")
      (node (ref "R18") (pin "1") (pinfunction "1_1") (pintype "passive"))
      (node (ref "USB") (pin "A") (pinfunction "A_A") (pintype "passive"))
    )
    (net (code "129") (name "Net-(R19-Pad1)") (class "Default")
      (node (ref "R19") (pin "1") (pinfunction "1_1") (pintype "passive"))
      (node (ref "R22") (pin "1") (pinfunction "1_1") (pintype "passive"))
      (node (ref "XMIN") (pin "1") (pinfunction "1_1") (pintype "passive"))
    )
    (net (code "130") (name "Net-(R20-Pad1)") (class "Default")
      (node (ref "R20") (pin "1") (pinfunction "1_1") (pintype "passive"))
      (node (ref "X6") (pin "D+") (pinfunction "D+_D+") (pintype "bidirectional"))
    )
    (net (code "131") (name "Net-(R21-Pad1)") (class "Default")
      (node (ref "R21") (pin "1") (pinfunction "1_1") (pintype "passive"))
      (node (ref "X6") (pin "D-") (pinfunction "D-_D-") (pintype "bidirectional"))
    )
    (net (code "132") (name "Net-(R24-Pad1)") (class "Default")
      (node (ref "R24") (pin "1") (pinfunction "1_1") (pintype "passive"))
      (node (ref "R25") (pin "1") (pinfunction "1_1") (pintype "passive"))
      (node (ref "XMAX") (pin "1") (pinfunction "1_1") (pintype "passive"))
    )
    (net (code "133") (name "Net-(R27-Pad1)") (class "Default")
      (node (ref "R27") (pin "1") (pinfunction "1_1") (pintype "passive"))
      (node (ref "R28") (pin "1") (pinfunction "1_1") (pintype "passive"))
      (node (ref "YMIN") (pin "1") (pinfunction "1_1") (pintype "passive"))
    )
    (net (code "134") (name "Net-(R34-Pad1)") (class "Default")
      (node (ref "R34") (pin "1") (pinfunction "1_1") (pintype "passive"))
      (node (ref "R36") (pin "1") (pinfunction "1_1") (pintype "passive"))
      (node (ref "YMAX") (pin "1") (pinfunction "1_1") (pintype "passive"))
    )
    (net (code "135") (name "Net-(R40-Pad1)") (class "Default")
      (node (ref "R40") (pin "1") (pinfunction "1_1") (pintype "passive"))
      (node (ref "R43") (pin "1") (pinfunction "1_1") (pintype "passive"))
      (node (ref "ZMIN") (pin "1") (pinfunction "1_1") (pintype "passive"))
    )
    (net (code "136") (name "Net-(R41-Pad2)") (class "Default")
      (node (ref "R41") (pin "2") (pinfunction "2_2") (pintype "passive"))
      (node (ref "R42") (pin "2") (pinfunction "2_2") (pintype "passive"))
      (node (ref "SJ1") (pin "2") (pinfunction "2_2") (pintype "passive"))
    )
    (net (code "137") (name "Net-(R44-Pad1)") (class "Default")
      (node (ref "R44") (pin "1") (pinfunction "1_1") (pintype "passive"))
      (node (ref "R45") (pin "1") (pinfunction "1_1") (pintype "passive"))
      (node (ref "ZMAX") (pin "1") (pinfunction "1_1") (pintype "passive"))
    )
    (net (code "138") (name "Net-(R54-Pad1)") (class "Default")
      (node (ref "R54") (pin "1") (pinfunction "1_1") (pintype "passive"))
      (node (ref "VBB") (pin "A") (pinfunction "A_A") (pintype "passive"))
    )
    (net (code "139") (name "Net-(X2F-S)") (class "Default")
      (node (ref "PS_ON") (pin "1") (pinfunction "1_1") (pintype "passive"))
      (node (ref "X2") (pin "14") (pinfunction "S_14") (pintype "passive"))
    )
    (net (code "140") (name "Net-(X5B-SK)") (class "Default")
      (node (ref "BIG") (pin "C") (pinfunction "C_C") (pintype "passive"))
      (node (ref "Q3") (pin "D") (pinfunction "D_D") (pintype "passive"))
      (node (ref "X5") (pin "2") (pinfunction "SK_2") (pintype "passive"))
    )
    (net (code "141") (name "VUSB") (class "Default")
      (node (ref "R18") (pin "2") (pinfunction "2_2") (pintype "passive"))
      (node (ref "X6") (pin "VBUS") (pinfunction "VBUS_VBUS") (pintype "bidirectional"))
    )
    (net (code "142") (name "unconnected-(H1-MOUNT-PadB3,2)") (class "Default")
      (node (ref "H1") (pin "B3,2") (pinfunction "MOUNT_B3,2") (pintype "passive"))
    )
    (net (code "143") (name "unconnected-(H2-MOUNT-PadB3,2)") (class "Default")
      (node (ref "H2") (pin "B3,2") (pinfunction "MOUNT_B3,2") (pintype "passive"))
    )
    (net (code "144") (name "unconnected-(H3-MOUNT-PadB3,2)") (class "Default")
      (node (ref "H3") (pin "B3,2") (pinfunction "MOUNT_B3,2") (pintype "passive"))
    )
    (net (code "145") (name "unconnected-(H4-MOUNT-PadB3,2)") (class "Default")
      (node (ref "H4") (pin "B3,2") (pinfunction "MOUNT_B3,2") (pintype "passive"))
    )
    (net (code "146") (name "unconnected-(IC2B-P$2-Pad5)") (class "Default")
      (node (ref "IC2") (pin "5") (pinfunction "P$2_5") (pintype "bidirectional"))
    )
    (net (code "147") (name "unconnected-(LPC1-Pad29)") (class "Default")
      (node (ref "LPC1") (pin "29") (pinfunction "29_29") (pintype "passive"))
    )
    (net (code "148") (name "unconnected-(LPC1-Pad30)") (class "Default")
      (node (ref "LPC1") (pin "30") (pinfunction "30_30") (pintype "passive"))
    )
    (net (code "149") (name "unconnected-(LPC1-Pad31)") (class "Default")
      (node (ref "LPC1") (pin "31") (pinfunction "31_31") (pintype "passive"))
    )
    (net (code "150") (name "unconnected-(M1-FAULT-Pad2)") (class "Default")
      (node (ref "M1") (pin "2") (pinfunction "FAULT_2") (pintype "output"))
    )
    (net (code "151") (name "unconnected-(M2-FAULT-Pad2)") (class "Default")
      (node (ref "M2") (pin "2") (pinfunction "FAULT_2") (pintype "output"))
    )
    (net (code "152") (name "unconnected-(M3-FAULT-Pad2)") (class "Default")
      (node (ref "M3") (pin "2") (pinfunction "FAULT_2") (pintype "output"))
    )
    (net (code "153") (name "unconnected-(M4-FAULT-Pad2)") (class "Default")
      (node (ref "M4") (pin "2") (pinfunction "FAULT_2") (pintype "output"))
    )
    (net (code "154") (name "unconnected-(RJ1-PadNC)") (class "Default")
      (node (ref "RJ1") (pin "NC") (pinfunction "NC_NC") (pintype "bidirectional"))
    )
    (net (code "155") (name "unconnected-(U1-NC-Pad1)") (class "Default")
      (node (ref "U1") (pin "1") (pinfunction "NC_1") (pintype "bidirectional"))
    )
    (net (code "156") (name "unconnected-(U1-RSV-Pad8)") (class "Default")
      (node (ref "U1") (pin "8") (pinfunction "RSV_8") (pintype "bidirectional"))
    )
  )
)
